# Projects.net
KiCad netlist of a schematic drawn in EAGLE
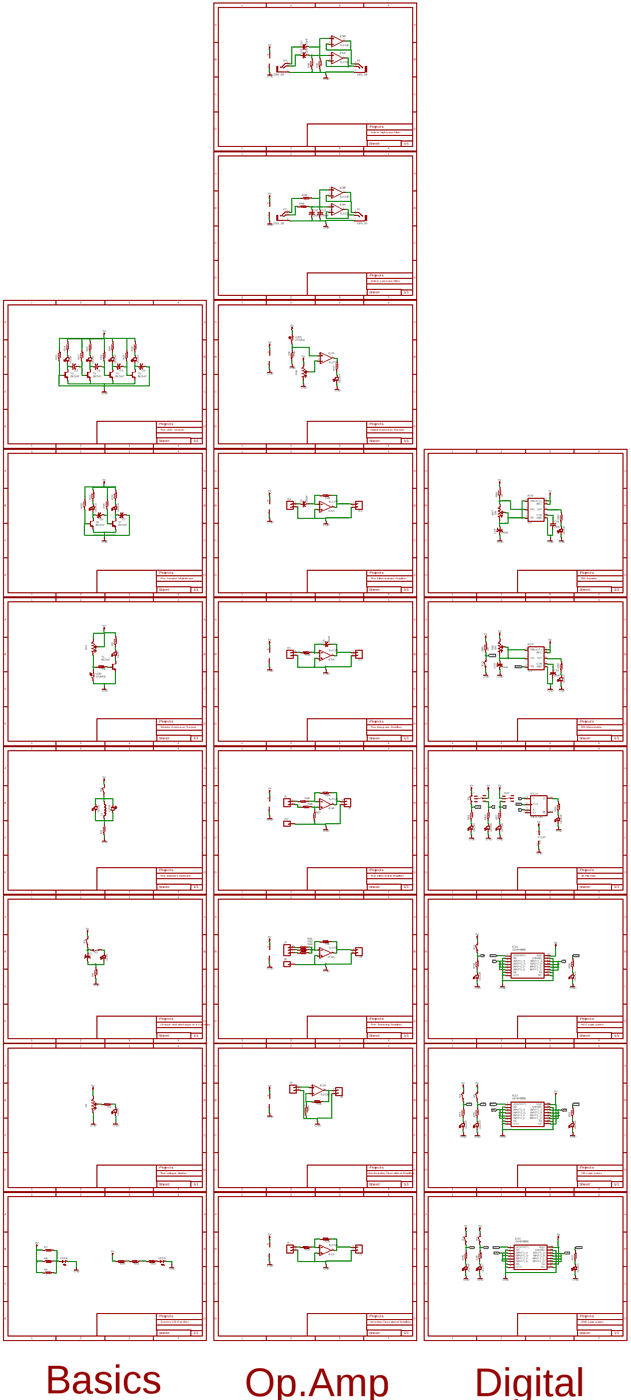
[diagram p0: schematic, sheet 1, overview]
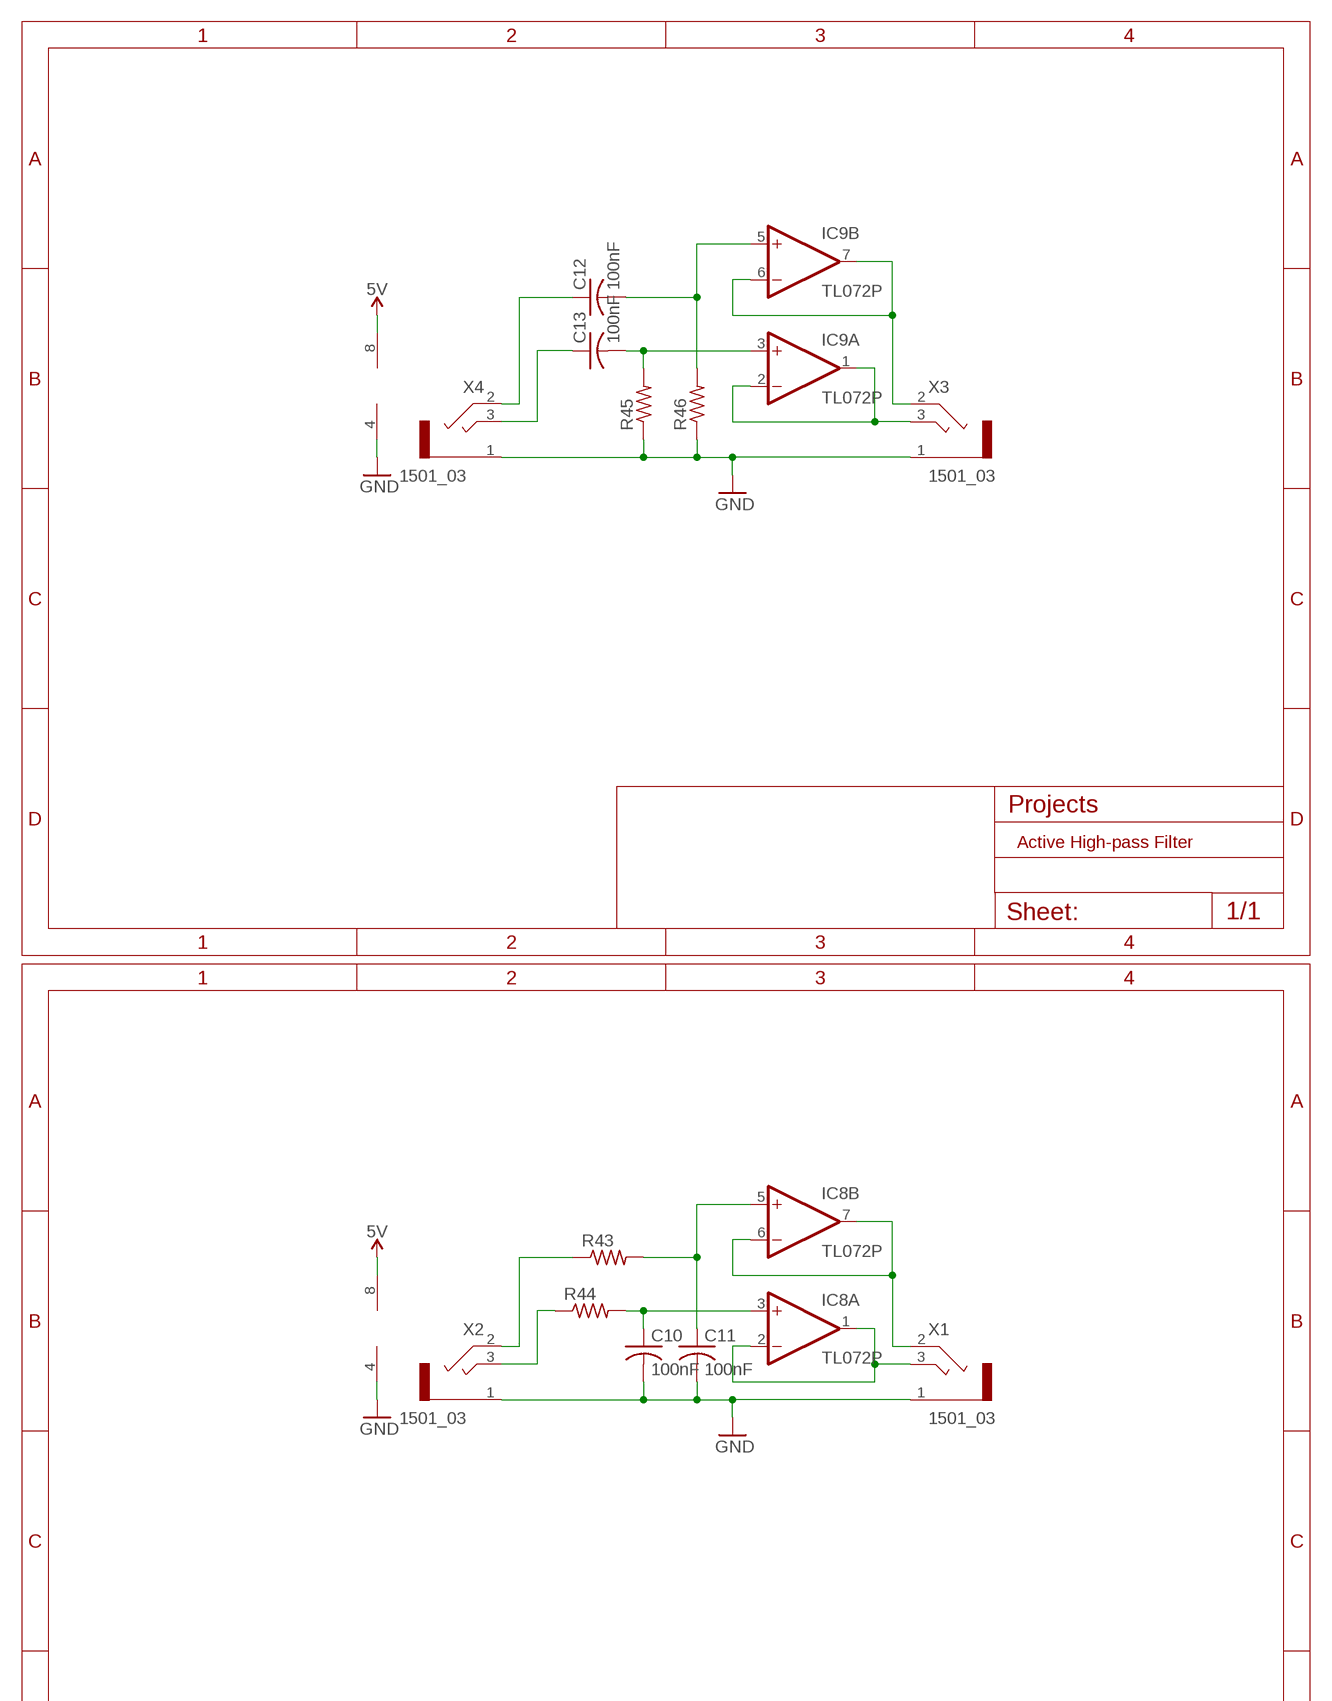
[diagram p1: schematic, sheet 1, part 1 of 7]
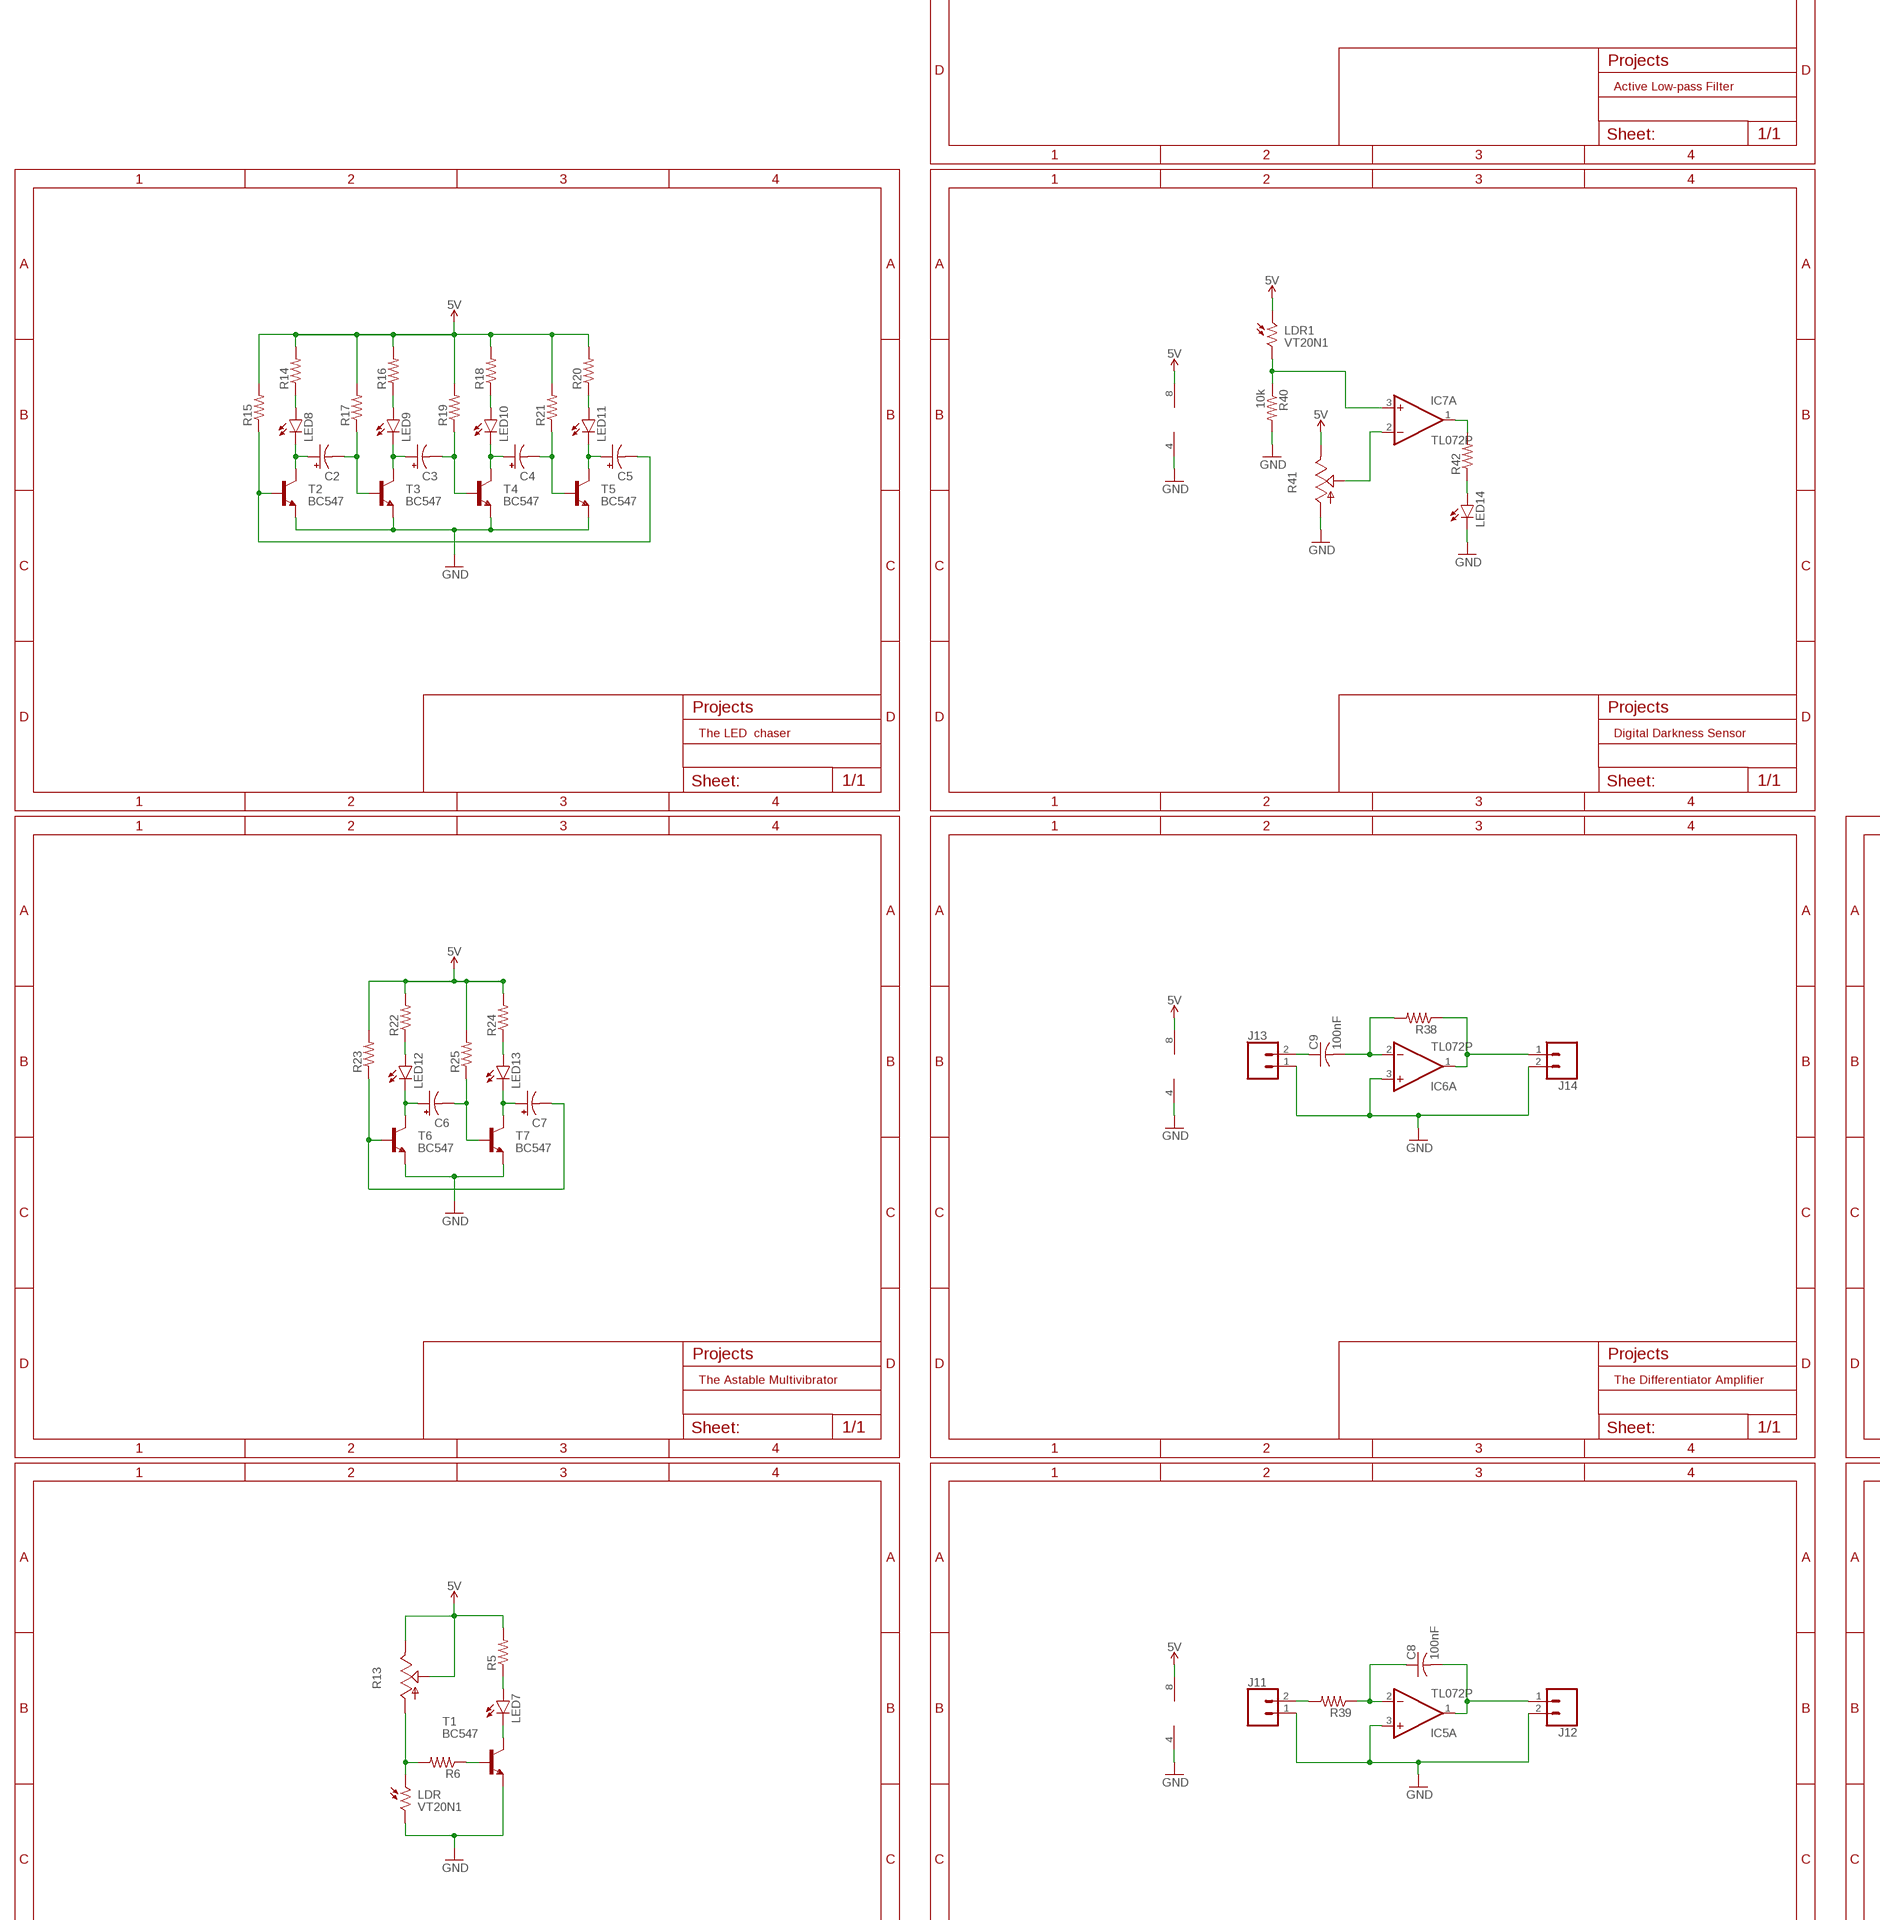
[diagram p2: schematic, sheet 1, part 2 of 7]
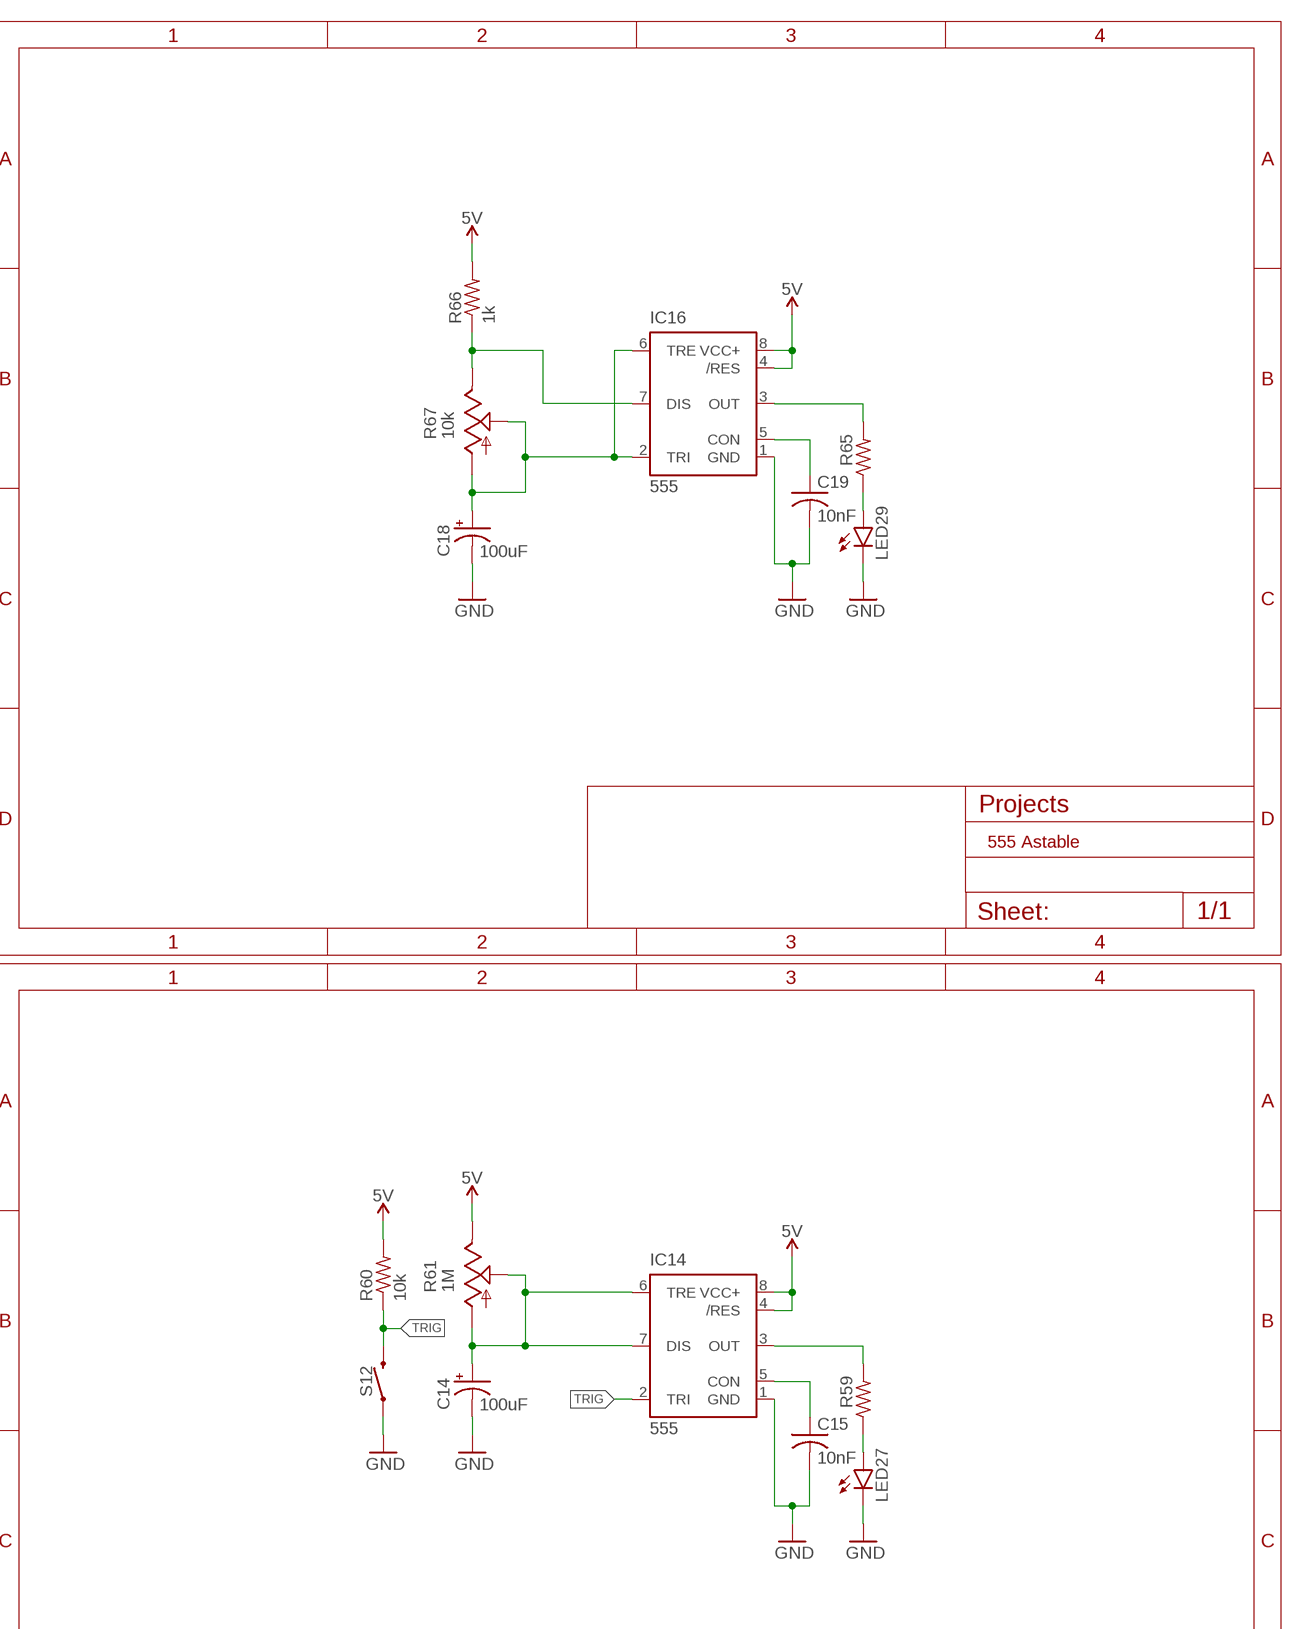
[diagram p3: schematic, sheet 1, part 3 of 7]
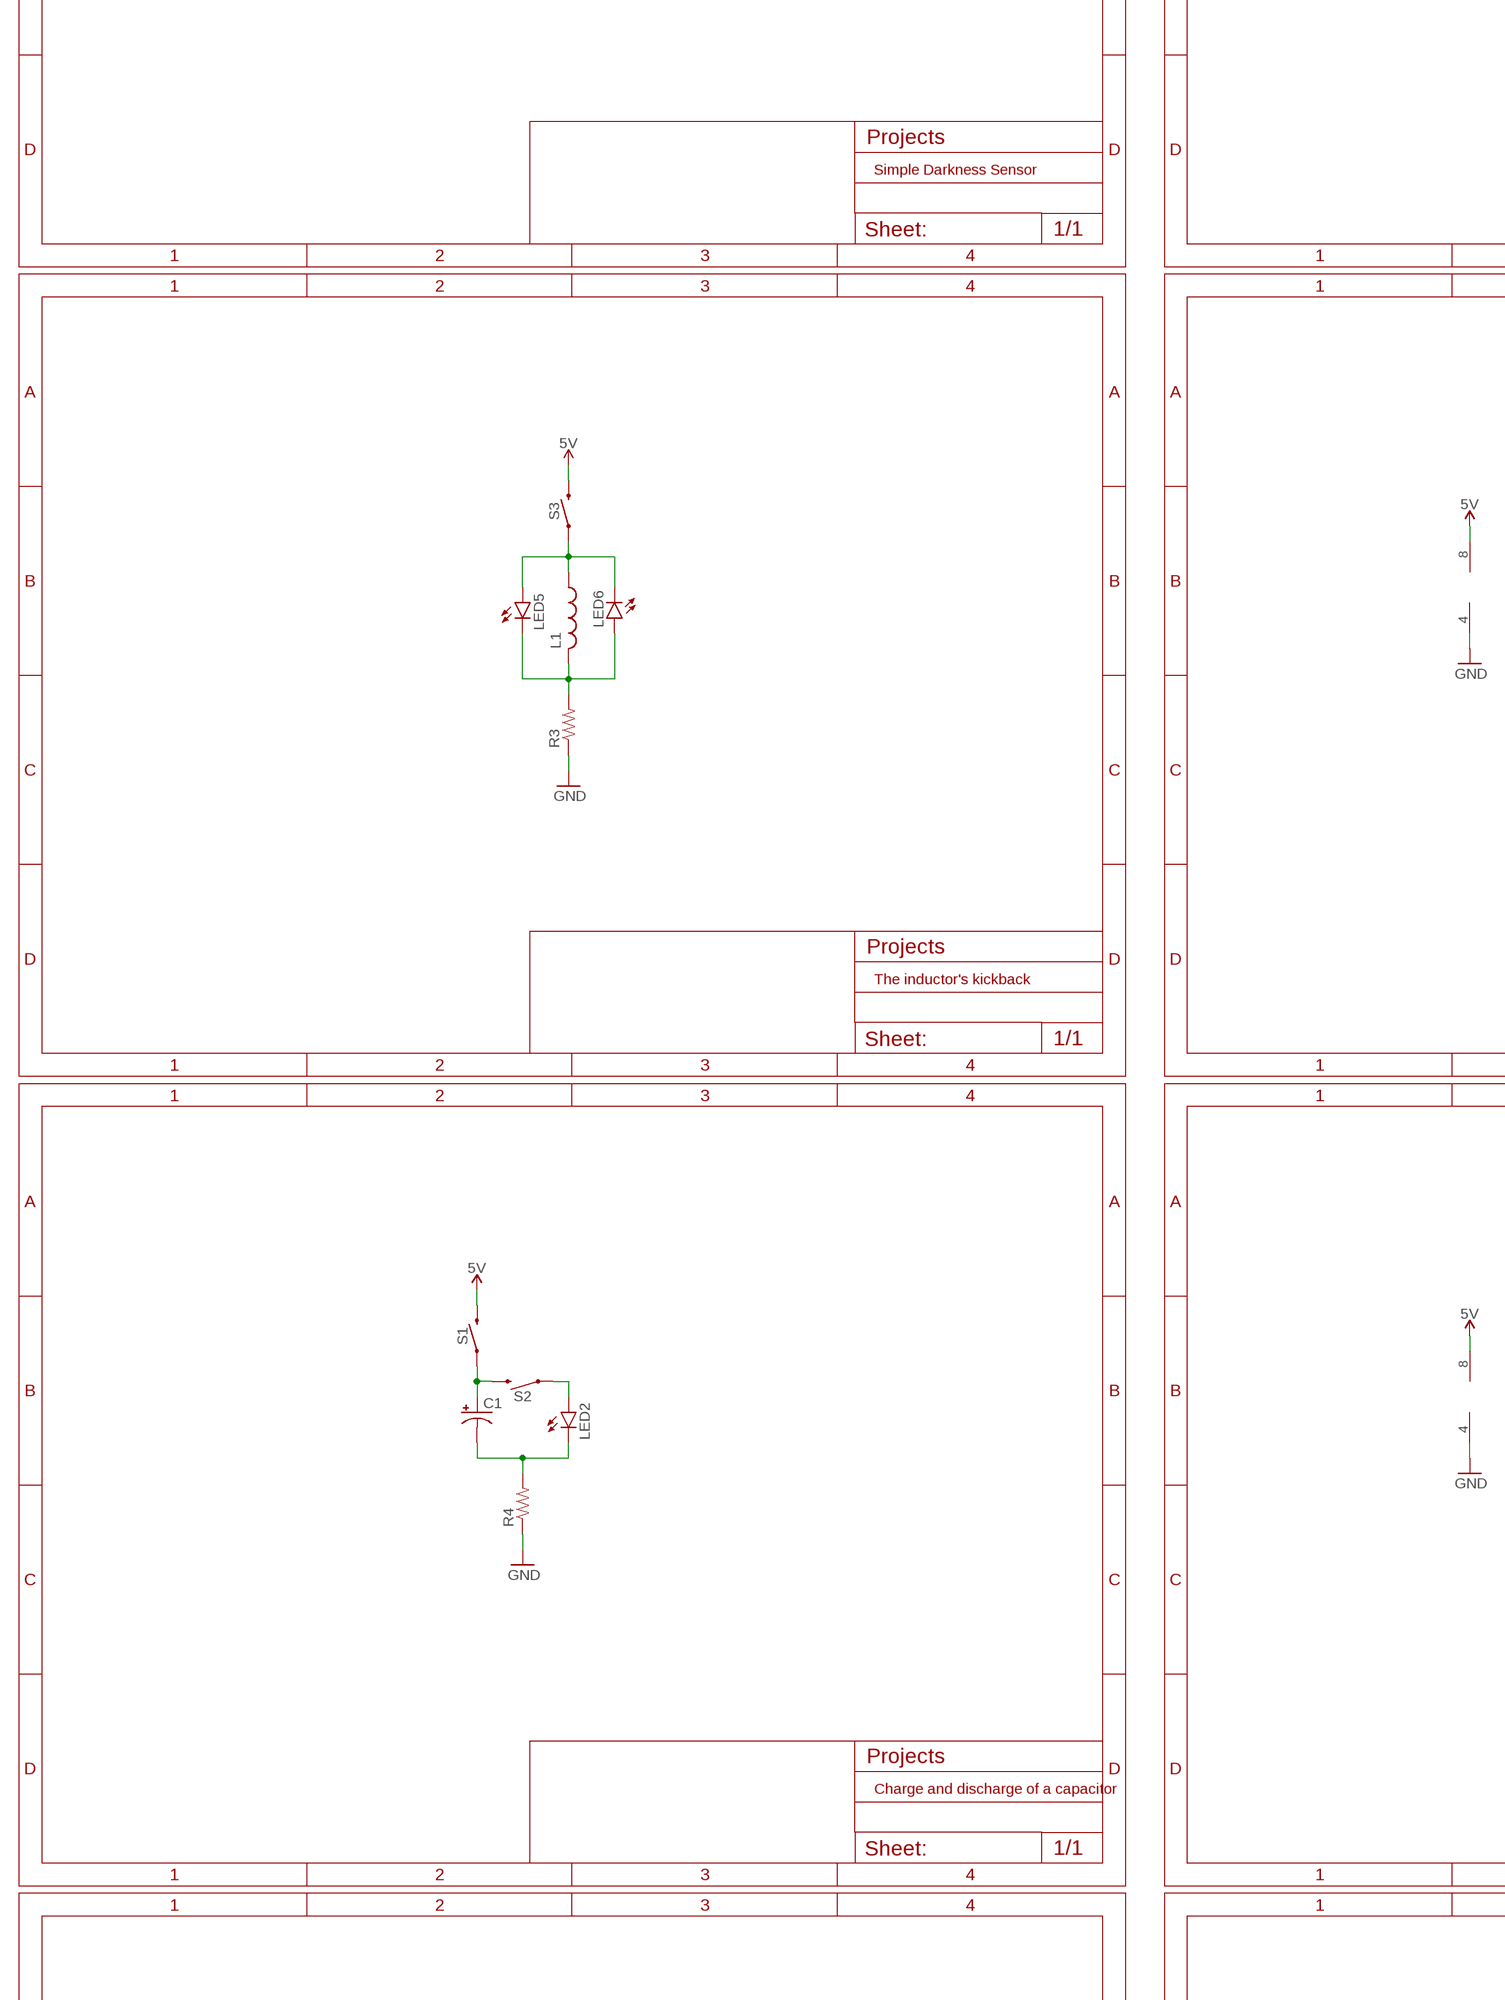
[diagram p4: schematic, sheet 1, part 4 of 7]
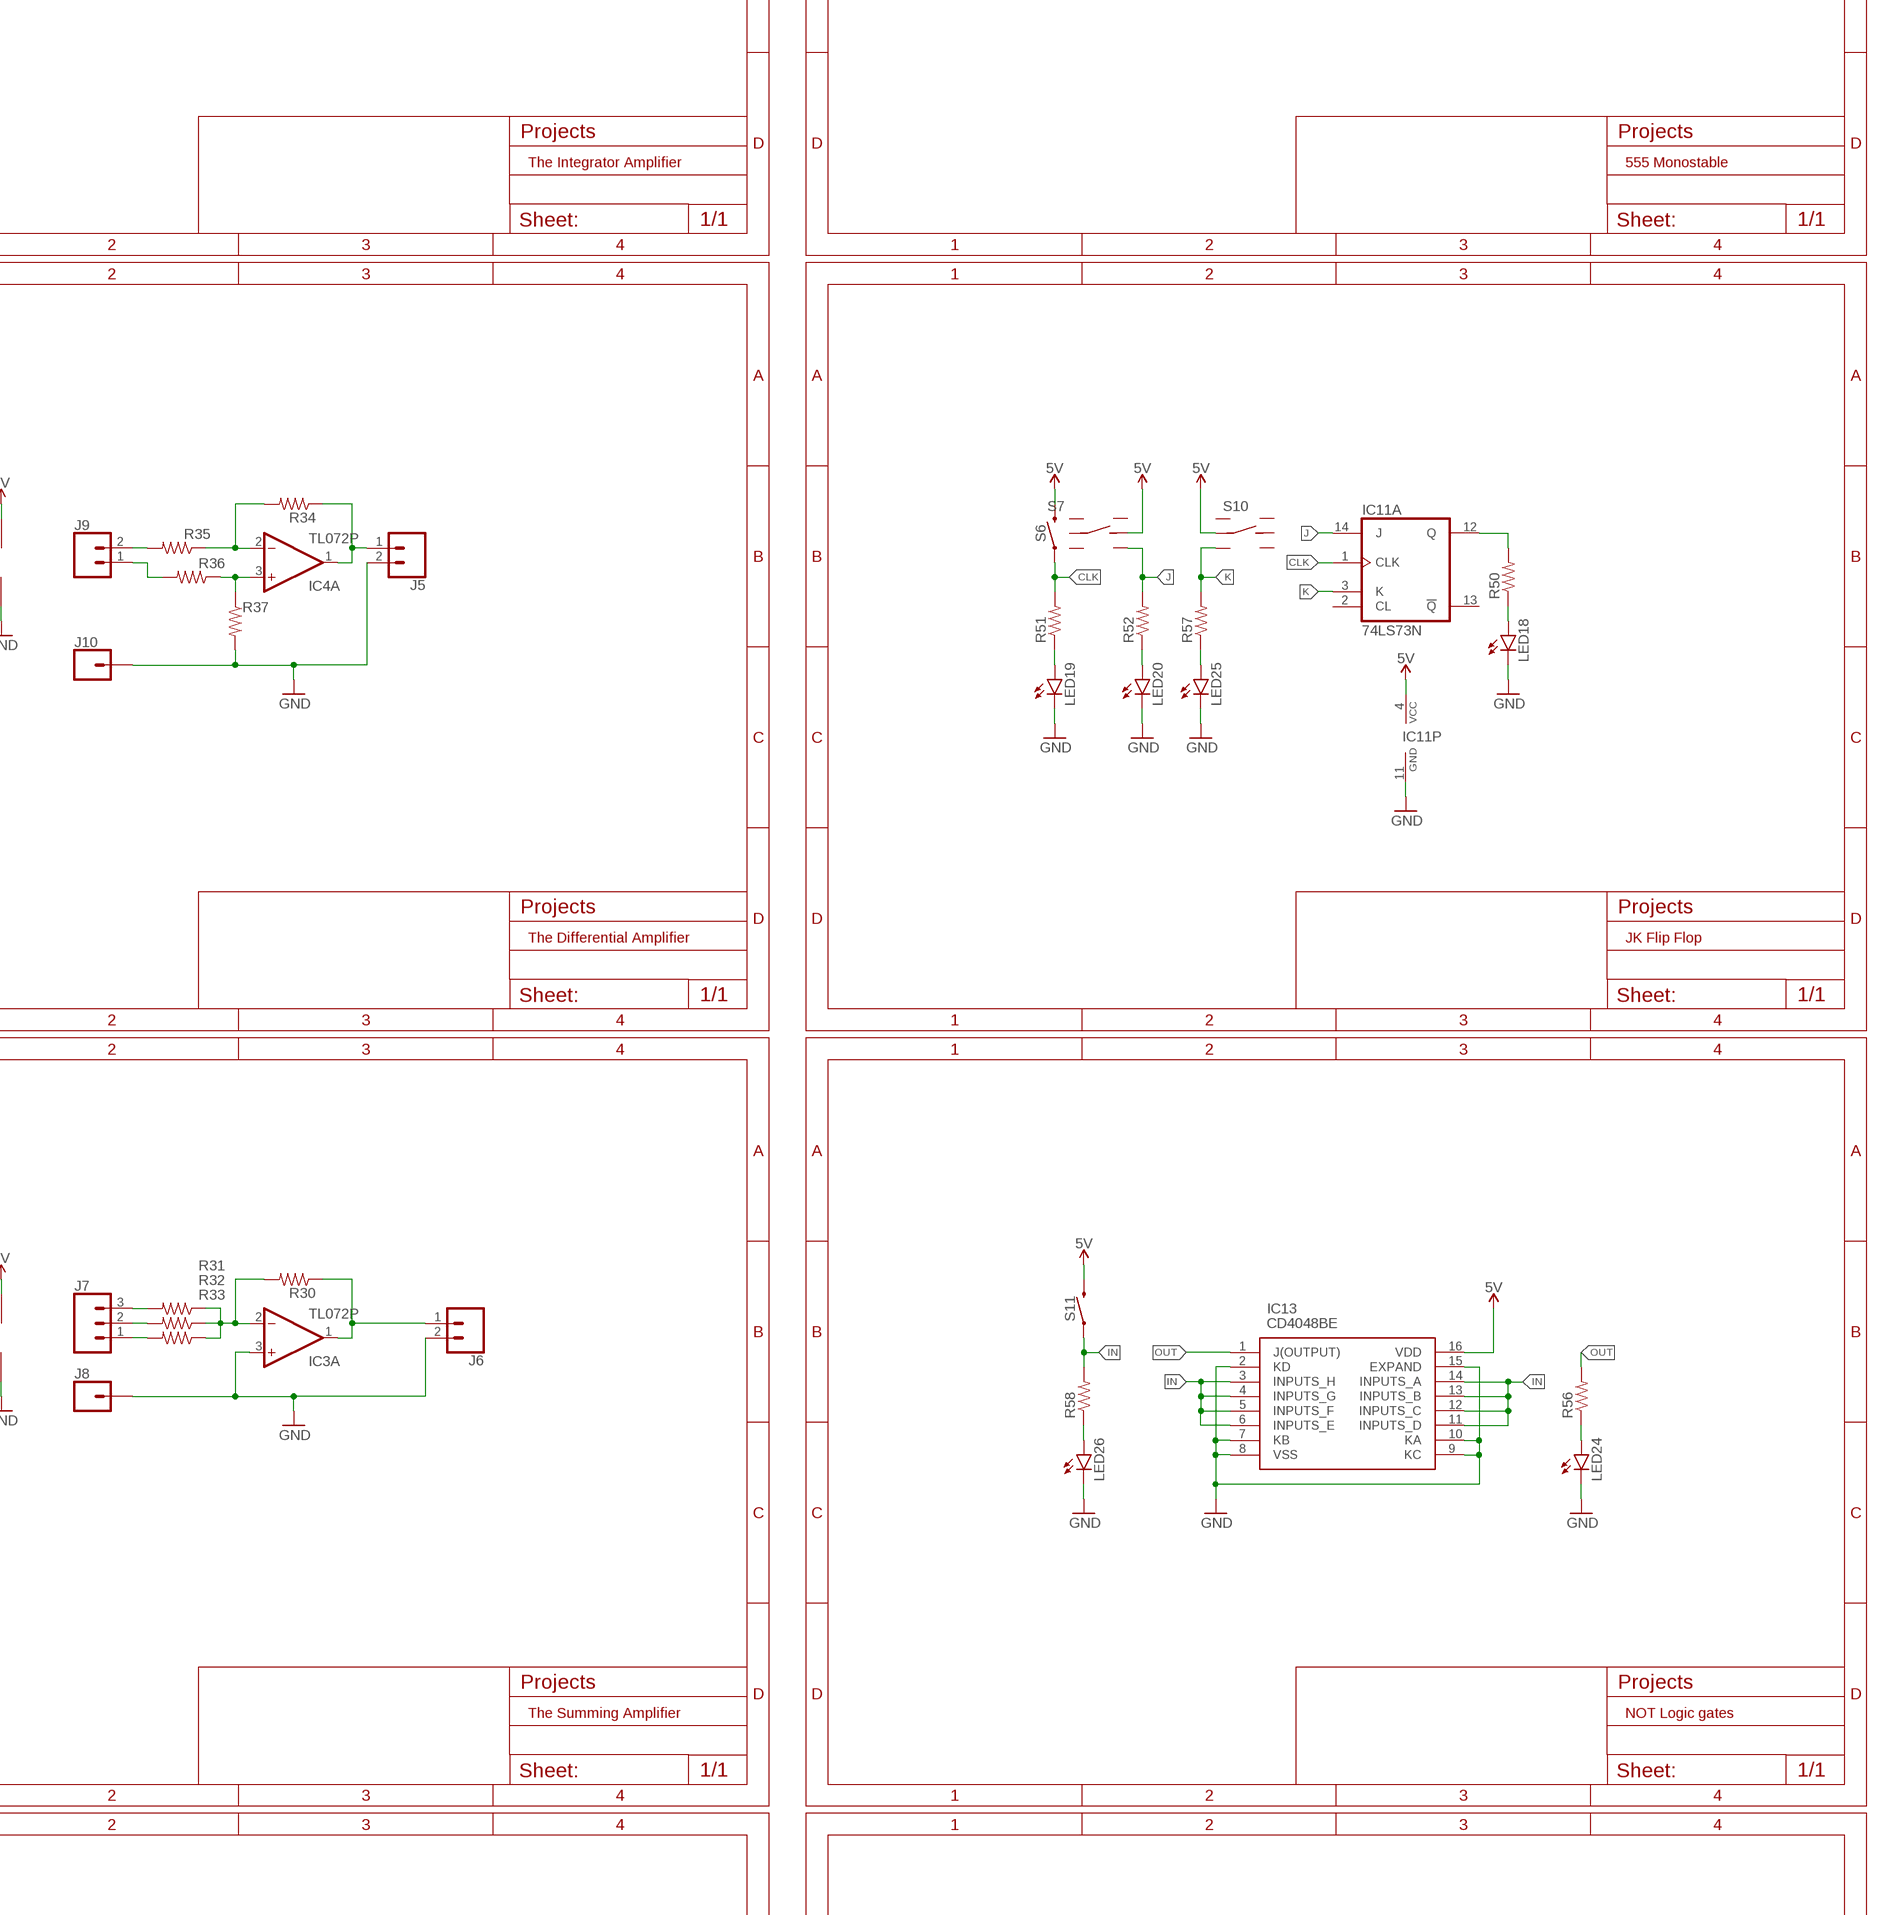
[diagram p5: schematic, sheet 1, part 5 of 7]
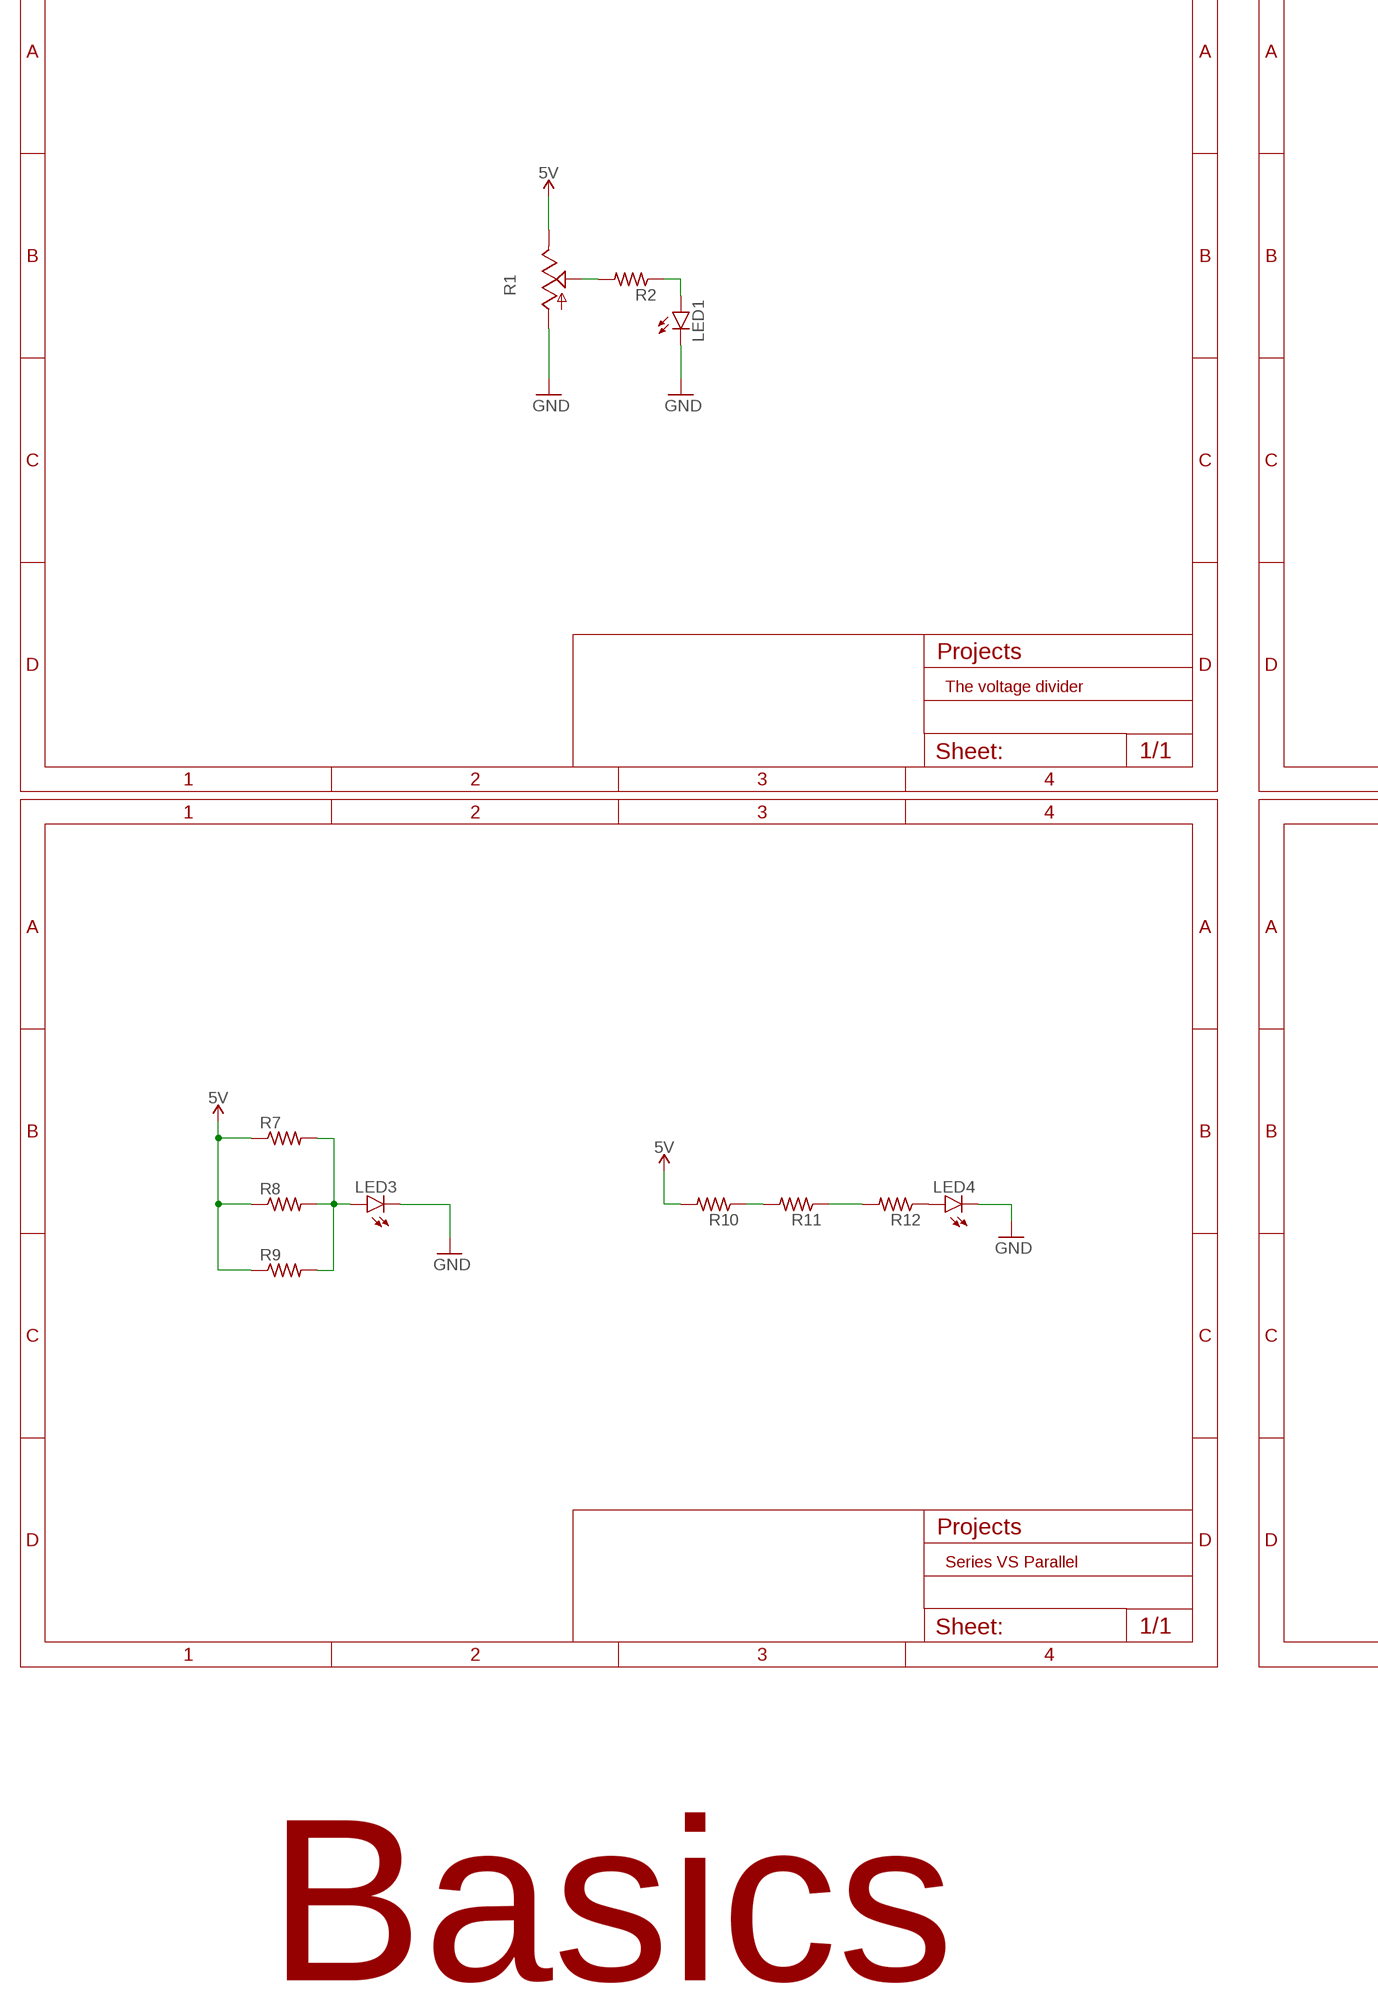
[diagram p6: schematic, sheet 1, part 6 of 7]
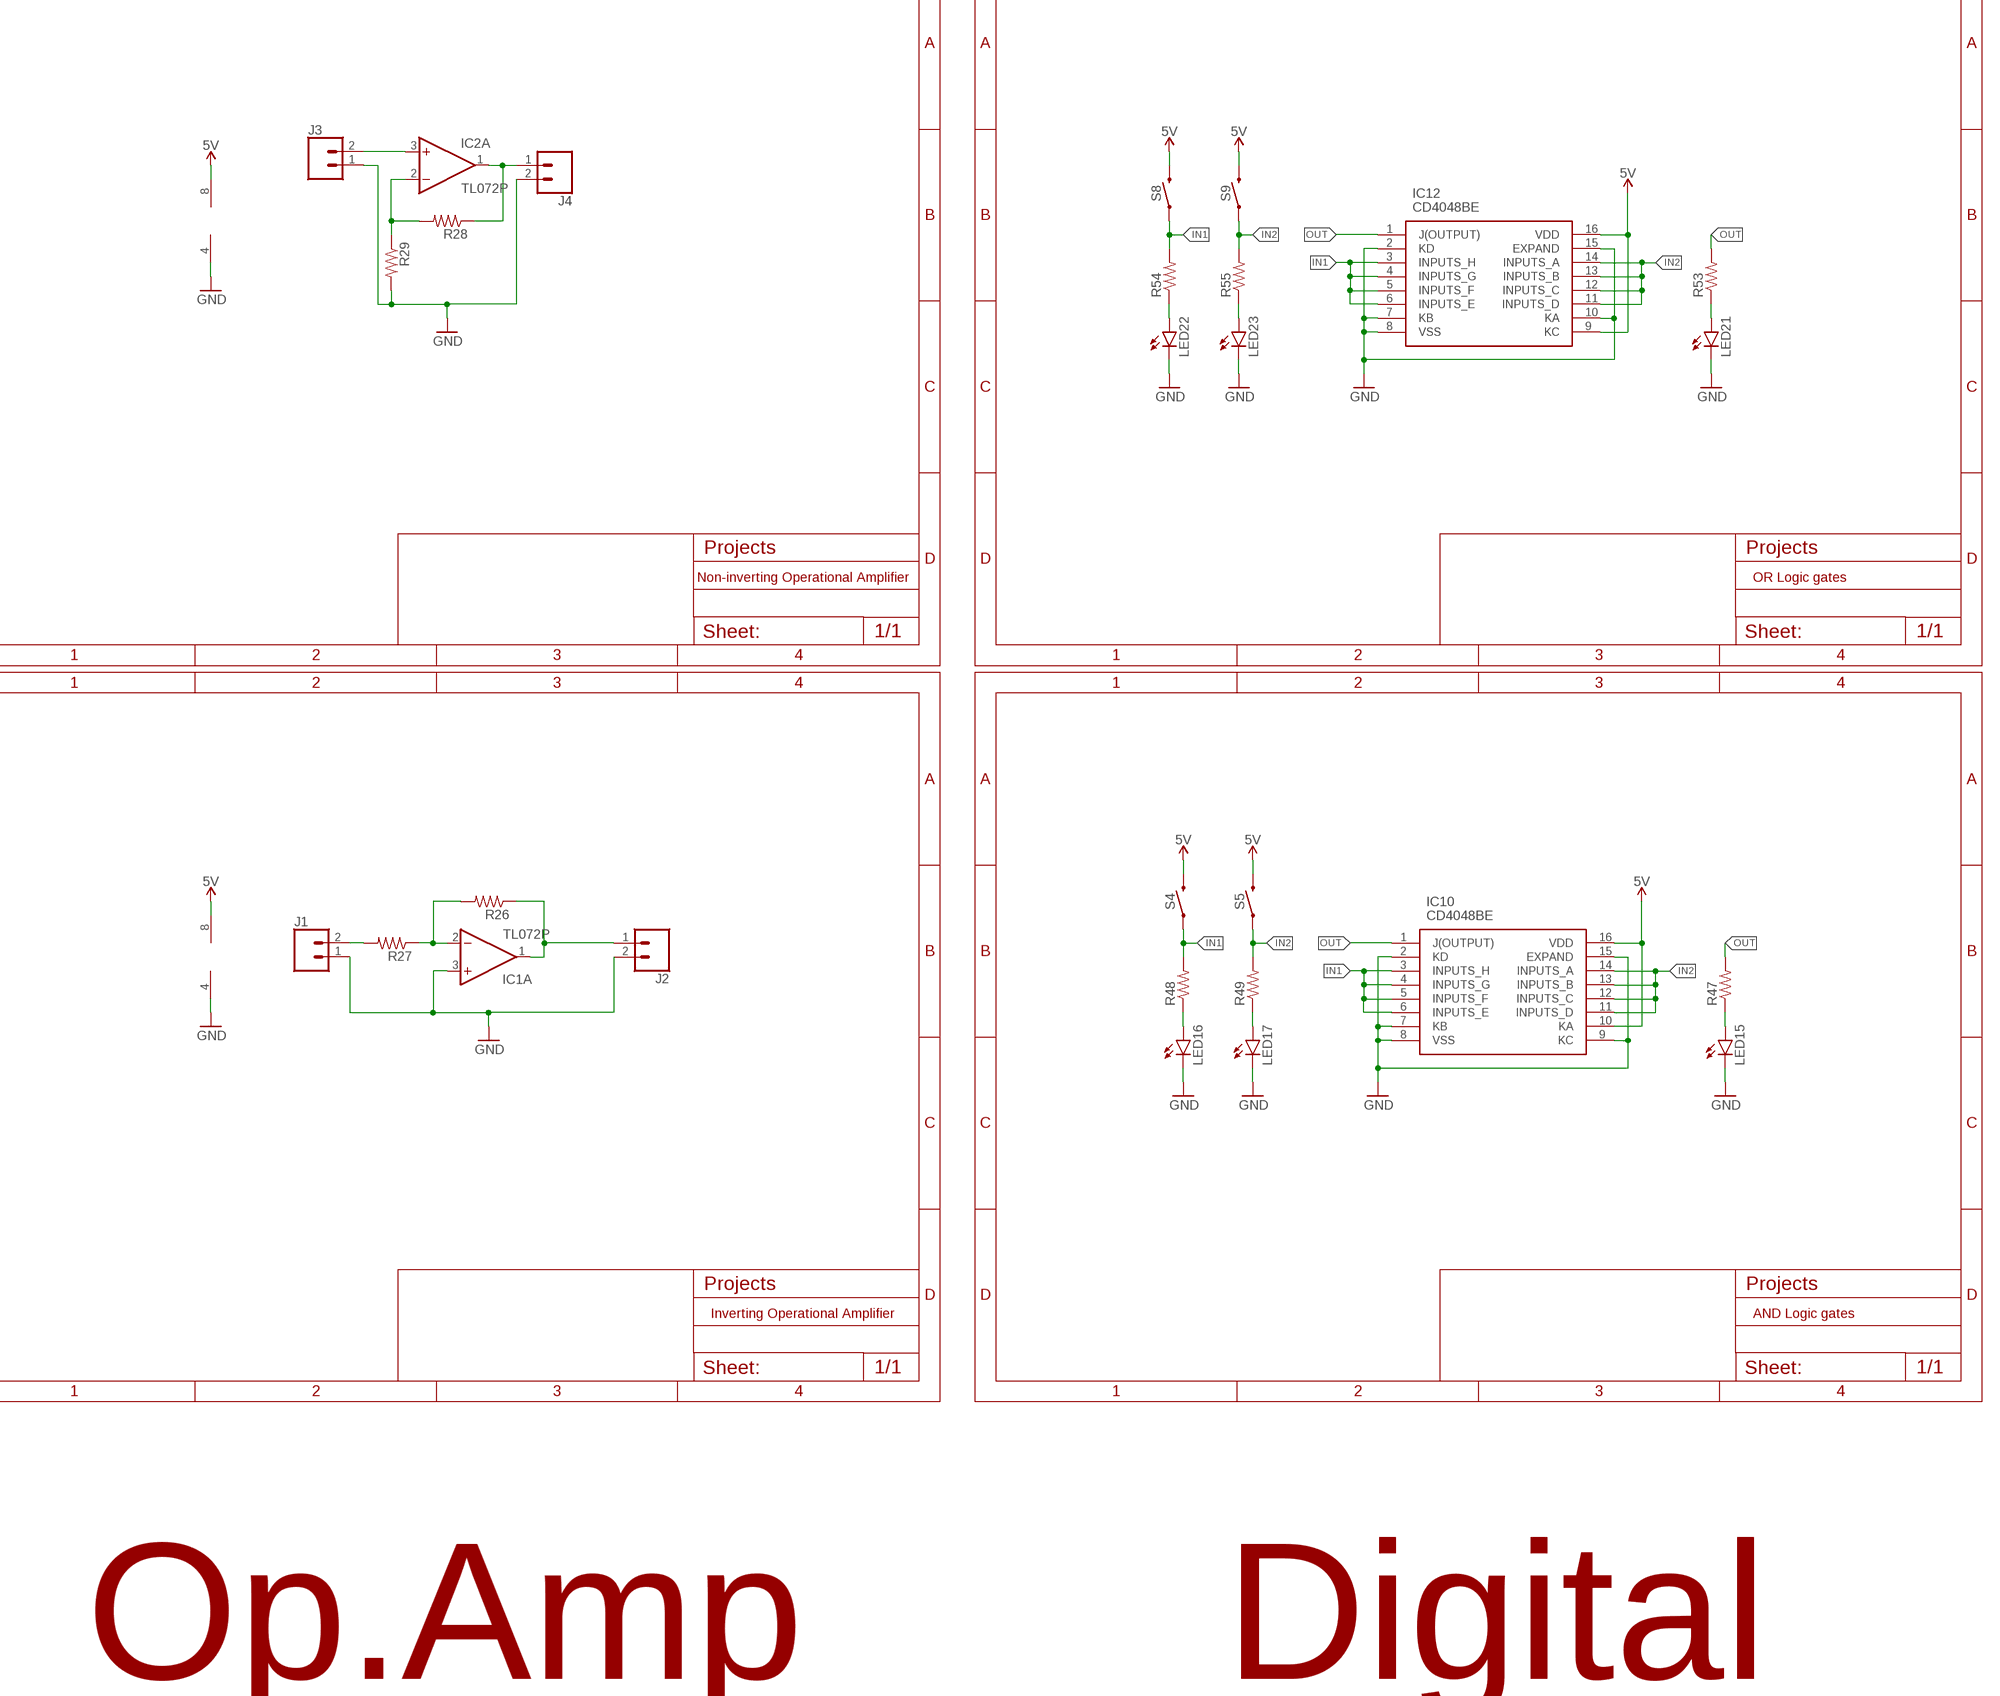
[diagram p7: schematic, sheet 1, part 7 of 7]

(export (version "E")
  (design (tool "Eeschema 10.0.6"))
  (components
    (comp (ref "C1")
      (value "CPOL-USE5-10.5")
      (footprint "eagle-import:E5-10,5")
      (libsource (lib "eagle-import") (part "CPOL-USE5-10.5"))
    )
    (comp (ref "C2")
      (value "CPOL-USE2.5-7")
      (footprint "eagle-import:E2,5-7")
      (libsource (lib "eagle-import") (part "rcl_334_CPOL-USE2.5-7"))
    )
    (comp (ref "C3")
      (value "CPOL-USE2.5-7")
      (footprint "eagle-import:E2,5-7")
      (libsource (lib "eagle-import") (part "rcl_334_CPOL-USE2.5-7"))
    )
    (comp (ref "C4")
      (value "CPOL-USE2.5-7")
      (footprint "eagle-import:E2,5-7")
      (libsource (lib "eagle-import") (part "rcl_334_CPOL-USE2.5-7"))
    )
    (comp (ref "C5")
      (value "CPOL-USE2.5-7")
      (footprint "eagle-import:E2,5-7")
      (libsource (lib "eagle-import") (part "rcl_334_CPOL-USE2.5-7"))
    )
    (comp (ref "C6")
      (value "CPOL-USE2.5-7")
      (footprint "eagle-import:E2,5-7")
      (libsource (lib "eagle-import") (part "rcl_334_CPOL-USE2.5-7"))
    )
    (comp (ref "C7")
      (value "CPOL-USE2.5-7")
      (footprint "eagle-import:E2,5-7")
      (libsource (lib "eagle-import") (part "rcl_334_CPOL-USE2.5-7"))
    )
    (comp (ref "C8")
      (value "100nF")
      (footprint "eagle-import:C050-025X075")
      (libsource (lib "eagle-import") (part "C-US050-025X075"))
    )
    (comp (ref "C9")
      (value "100nF")
      (footprint "eagle-import:C050-025X075")
      (libsource (lib "eagle-import") (part "C-US050-025X075"))
    )
    (comp (ref "C10")
      (value "100nF")
      (footprint "eagle-import:C050-025X075")
      (libsource (lib "eagle-import") (part "C-US050-025X075"))
    )
    (comp (ref "C11")
      (value "100nF")
      (footprint "eagle-import:C050-025X075")
      (libsource (lib "eagle-import") (part "C-US050-025X075"))
    )
    (comp (ref "C12")
      (value "100nF")
      (footprint "eagle-import:C050-025X075")
      (libsource (lib "eagle-import") (part "C-US050-025X075"))
    )
    (comp (ref "C13")
      (value "100nF")
      (footprint "eagle-import:C050-025X075")
      (libsource (lib "eagle-import") (part "C-US050-025X075"))
    )
    (comp (ref "C14")
      (value "100uF")
      (footprint "eagle-import:E2,5-7")
      (libsource (lib "eagle-import") (part "rcl_334_CPOL-USE2.5-7"))
    )
    (comp (ref "C15")
      (value "10nF")
      (footprint "eagle-import:C050-025X075")
      (libsource (lib "eagle-import") (part "C-US050-025X075"))
    )
    (comp (ref "C18")
      (value "100uF")
      (footprint "eagle-import:E2,5-7")
      (libsource (lib "eagle-import") (part "rcl_334_CPOL-USE2.5-7"))
    )
    (comp (ref "C19")
      (value "10nF")
      (footprint "eagle-import:C050-025X075")
      (libsource (lib "eagle-import") (part "C-US050-025X075"))
    )
    (comp (ref "IC1")
      (value "TL072P")
      (footprint "eagle-import:DIL08")
      (libsource (lib "eagle-import") (part "TL072P"))
    )
    (comp (ref "IC2")
      (value "TL072P")
      (footprint "eagle-import:DIL08")
      (libsource (lib "eagle-import") (part "TL072P"))
    )
    (comp (ref "IC3")
      (value "TL072P")
      (footprint "eagle-import:DIL08")
      (libsource (lib "eagle-import") (part "TL072P"))
    )
    (comp (ref "IC4")
      (value "TL072P")
      (footprint "eagle-import:DIL08")
      (libsource (lib "eagle-import") (part "TL072P"))
    )
    (comp (ref "IC5")
      (value "TL072P")
      (footprint "eagle-import:DIL08")
      (libsource (lib "eagle-import") (part "TL072P"))
    )
    (comp (ref "IC6")
      (value "TL072P")
      (footprint "eagle-import:DIL08")
      (libsource (lib "eagle-import") (part "TL072P"))
    )
    (comp (ref "IC7")
      (value "TL072P")
      (footprint "eagle-import:DIL08")
      (libsource (lib "eagle-import") (part "TL072P"))
    )
    (comp (ref "IC8")
      (value "TL072P")
      (footprint "eagle-import:DIL08")
      (libsource (lib "eagle-import") (part "TL072P"))
    )
    (comp (ref "IC9")
      (value "TL072P")
      (footprint "eagle-import:DIL08")
      (libsource (lib "eagle-import") (part "TL072P"))
    )
    (comp (ref "IC10")
      (value "CD4048BE")
      (footprint "eagle-import:DIP794W53P254L1930H508Q16N")
      (fields (field (name "MOUSER_PART_NUMBER") "595-CD4048BE"))
      (libsource (lib "eagle-import") (part "CD4048BE"))
    )
    (comp (ref "IC11")
      (value "74LS73N")
      (footprint "eagle-import:DIL14")
      (libsource (lib "eagle-import") (part "7473NLS"))
    )
    (comp (ref "IC12")
      (value "CD4048BE")
      (footprint "eagle-import:DIP794W53P254L1930H508Q16N")
      (fields (field (name "MOUSER_PART_NUMBER") "595-CD4048BE"))
      (libsource (lib "eagle-import") (part "CD4048BE"))
    )
    (comp (ref "IC13")
      (value "CD4048BE")
      (footprint "eagle-import:DIP794W53P254L1930H508Q16N")
      (fields (field (name "MOUSER_PART_NUMBER") "595-CD4048BE"))
      (libsource (lib "eagle-import") (part "CD4048BE"))
    )
    (comp (ref "IC14")
      (value "555")
      (footprint "eagle-import:DIP08-KIT")
      (libsource (lib "eagle-import") (part "555KIT"))
    )
    (comp (ref "IC16")
      (value "555")
      (footprint "eagle-import:DIP08-KIT")
      (libsource (lib "eagle-import") (part "555KIT"))
    )
    (comp (ref "J1")
      (value "CONN_02")
      (footprint "eagle-import:1X02")
      (libsource (lib "eagle-import") (part "CONN_02"))
    )
    (comp (ref "J2")
      (value "CONN_02")
      (footprint "eagle-import:1X02")
      (libsource (lib "eagle-import") (part "CONN_02"))
    )
    (comp (ref "J3")
      (value "CONN_02")
      (footprint "eagle-import:1X02")
      (libsource (lib "eagle-import") (part "CONN_02"))
    )
    (comp (ref "J4")
      (value "CONN_02")
      (footprint "eagle-import:1X02")
      (libsource (lib "eagle-import") (part "CONN_02"))
    )
    (comp (ref "J5")
      (value "CONN_02")
      (footprint "eagle-import:1X02")
      (libsource (lib "eagle-import") (part "CONN_02"))
    )
    (comp (ref "J6")
      (value "CONN_02")
      (footprint "eagle-import:1X02")
      (libsource (lib "eagle-import") (part "CONN_02"))
    )
    (comp (ref "J7")
      (value "455-1750-1-ND")
      (footprint "eagle-import:1X03")
      (libsource (lib "eagle-import") (part "CONN_03"))
    )
    (comp (ref "J8")
      (value "CONN_01")
      (footprint "eagle-import:1X01")
      (libsource (lib "eagle-import") (part "CONN_01"))
    )
    (comp (ref "J9")
      (value "CONN_02")
      (footprint "eagle-import:1X02")
      (libsource (lib "eagle-import") (part "CONN_02"))
    )
    (comp (ref "J10")
      (value "CONN_01")
      (footprint "eagle-import:1X01")
      (libsource (lib "eagle-import") (part "CONN_01"))
    )
    (comp (ref "J11")
      (value "CONN_02")
      (footprint "eagle-import:1X02")
      (libsource (lib "eagle-import") (part "CONN_02"))
    )
    (comp (ref "J12")
      (value "CONN_02")
      (footprint "eagle-import:1X02")
      (libsource (lib "eagle-import") (part "CONN_02"))
    )
    (comp (ref "J13")
      (value "CONN_02")
      (footprint "eagle-import:1X02")
      (libsource (lib "eagle-import") (part "CONN_02"))
    )
    (comp (ref "J14")
      (value "CONN_02")
      (footprint "eagle-import:1X02")
      (libsource (lib "eagle-import") (part "CONN_02"))
    )
    (comp (ref "L1")
      (value "L-US6000-XXX-RC")
      (footprint "eagle-import:6000-XXXX-RC")
      (libsource (lib "eagle-import") (part "L-US6000-XXX-RC"))
    )
    (comp (ref "LDR")
      (value "VT20N1")
      (footprint "eagle-import:TO46-VT200")
      (libsource (lib "eagle-import") (part "VT20N1"))
    )
    (comp (ref "LDR1")
      (value "VT20N1")
      (footprint "eagle-import:TO46-VT200")
      (libsource (lib "eagle-import") (part "VT20N1"))
    )
    (comp (ref "LED1")
      (value "LED5MM")
      (footprint "eagle-import:LED5MM")
      (libsource (lib "eagle-import") (part "LED5MM"))
    )
    (comp (ref "LED2")
      (value "LED5MM")
      (footprint "eagle-import:LED5MM")
      (libsource (lib "eagle-import") (part "LED5MM"))
    )
    (comp (ref "LED3")
      (value "LED5MM")
      (footprint "eagle-import:LED5MM")
      (libsource (lib "eagle-import") (part "LED5MM"))
    )
    (comp (ref "LED4")
      (value "LED5MM")
      (footprint "eagle-import:LED5MM")
      (libsource (lib "eagle-import") (part "LED5MM"))
    )
    (comp (ref "LED5")
      (value "LED5MM")
      (footprint "eagle-import:LED5MM")
      (libsource (lib "eagle-import") (part "LED5MM"))
    )
    (comp (ref "LED6")
      (value "LED5MM")
      (footprint "eagle-import:LED5MM")
      (libsource (lib "eagle-import") (part "LED5MM"))
    )
    (comp (ref "LED7")
      (value "LED5MM")
      (footprint "eagle-import:LED5MM")
      (libsource (lib "eagle-import") (part "LED5MM"))
    )
    (comp (ref "LED8")
      (value "LED5MM")
      (footprint "eagle-import:LED5MM")
      (libsource (lib "eagle-import") (part "LED5MM"))
    )
    (comp (ref "LED9")
      (value "LED5MM")
      (footprint "eagle-import:LED5MM")
      (libsource (lib "eagle-import") (part "LED5MM"))
    )
    (comp (ref "LED10")
      (value "LED5MM")
      (footprint "eagle-import:LED5MM")
      (libsource (lib "eagle-import") (part "LED5MM"))
    )
    (comp (ref "LED11")
      (value "LED5MM")
      (footprint "eagle-import:LED5MM")
      (libsource (lib "eagle-import") (part "LED5MM"))
    )
    (comp (ref "LED12")
      (value "LED5MM")
      (footprint "eagle-import:LED5MM")
      (libsource (lib "eagle-import") (part "LED5MM"))
    )
    (comp (ref "LED13")
      (value "LED5MM")
      (footprint "eagle-import:LED5MM")
      (libsource (lib "eagle-import") (part "LED5MM"))
    )
    (comp (ref "LED14")
      (value "LED5MM")
      (footprint "eagle-import:LED5MM")
      (libsource (lib "eagle-import") (part "LED5MM"))
    )
    (comp (ref "LED15")
      (value "LED5MM")
      (footprint "eagle-import:LED5MM")
      (libsource (lib "eagle-import") (part "LED5MM"))
    )
    (comp (ref "LED16")
      (value "LED5MM")
      (footprint "eagle-import:LED5MM")
      (libsource (lib "eagle-import") (part "LED5MM"))
    )
    (comp (ref "LED17")
      (value "LED5MM")
      (footprint "eagle-import:LED5MM")
      (libsource (lib "eagle-import") (part "LED5MM"))
    )
    (comp (ref "LED18")
      (value "LED5MM")
      (footprint "eagle-import:LED5MM")
      (libsource (lib "eagle-import") (part "LED5MM"))
    )
    (comp (ref "LED19")
      (value "LED5MM")
      (footprint "eagle-import:LED5MM")
      (libsource (lib "eagle-import") (part "LED5MM"))
    )
    (comp (ref "LED20")
      (value "LED5MM")
      (footprint "eagle-import:LED5MM")
      (libsource (lib "eagle-import") (part "LED5MM"))
    )
    (comp (ref "LED21")
      (value "LED5MM")
      (footprint "eagle-import:LED5MM")
      (libsource (lib "eagle-import") (part "LED5MM"))
    )
    (comp (ref "LED22")
      (value "LED5MM")
      (footprint "eagle-import:LED5MM")
      (libsource (lib "eagle-import") (part "LED5MM"))
    )
    (comp (ref "LED23")
      (value "LED5MM")
      (footprint "eagle-import:LED5MM")
      (libsource (lib "eagle-import") (part "LED5MM"))
    )
    (comp (ref "LED24")
      (value "LED5MM")
      (footprint "eagle-import:LED5MM")
      (libsource (lib "eagle-import") (part "LED5MM"))
    )
    (comp (ref "LED25")
      (value "LED5MM")
      (footprint "eagle-import:LED5MM")
      (libsource (lib "eagle-import") (part "LED5MM"))
    )
    (comp (ref "LED26")
      (value "LED5MM")
      (footprint "eagle-import:LED5MM")
      (libsource (lib "eagle-import") (part "LED5MM"))
    )
    (comp (ref "LED27")
      (value "LED5MM")
      (footprint "eagle-import:LED5MM")
      (libsource (lib "eagle-import") (part "LED5MM"))
    )
    (comp (ref "LED29")
      (value "LED5MM")
      (footprint "eagle-import:LED5MM")
      (libsource (lib "eagle-import") (part "LED5MM"))
    )
    (comp (ref "R1")
      (value "TRIM_US-S63P")
      (footprint "eagle-import:S63P")
      (libsource (lib "eagle-import") (part "TRIM_US-S63P"))
    )
    (comp (ref "R2")
      (value "R-US_0204/7")
      (footprint "eagle-import:0204_7")
      (libsource (lib "eagle-import") (part "R-US_0204/7"))
    )
    (comp (ref "R3")
      (value "R-US_0204/7")
      (footprint "eagle-import:0204_7")
      (libsource (lib "eagle-import") (part "R-US_0204/7"))
    )
    (comp (ref "R4")
      (value "R-US_0204/7")
      (footprint "eagle-import:0204_7")
      (libsource (lib "eagle-import") (part "R-US_0204/7"))
    )
    (comp (ref "R5")
      (value "R-US_0204/7")
      (footprint "eagle-import:0204_7")
      (libsource (lib "eagle-import") (part "R-US_0204/7"))
    )
    (comp (ref "R6")
      (value "R-US_0204/7")
      (footprint "eagle-import:0204_7")
      (libsource (lib "eagle-import") (part "R-US_0204/7"))
    )
    (comp (ref "R7")
      (value "R-US_0204/7")
      (footprint "eagle-import:0204_7")
      (libsource (lib "eagle-import") (part "R-US_0204/7"))
    )
    (comp (ref "R8")
      (value "R-US_0204/7")
      (footprint "eagle-import:0204_7")
      (libsource (lib "eagle-import") (part "R-US_0204/7"))
    )
    (comp (ref "R9")
      (value "R-US_0204/7")
      (footprint "eagle-import:0204_7")
      (libsource (lib "eagle-import") (part "R-US_0204/7"))
    )
    (comp (ref "R10")
      (value "R-US_0204/7")
      (footprint "eagle-import:0204_7")
      (libsource (lib "eagle-import") (part "R-US_0204/7"))
    )
    (comp (ref "R11")
      (value "R-US_0204/7")
      (footprint "eagle-import:0204_7")
      (libsource (lib "eagle-import") (part "R-US_0204/7"))
    )
    (comp (ref "R12")
      (value "R-US_0204/7")
      (footprint "eagle-import:0204_7")
      (libsource (lib "eagle-import") (part "R-US_0204/7"))
    )
    (comp (ref "R13")
      (value "TRIM_US-S63P")
      (footprint "eagle-import:S63P")
      (libsource (lib "eagle-import") (part "TRIM_US-S63P"))
    )
    (comp (ref "R14")
      (value "R-US_0204/7")
      (footprint "eagle-import:0204_7")
      (libsource (lib "eagle-import") (part "R-US_0204/7"))
    )
    (comp (ref "R15")
      (value "R-US_0204/7")
      (footprint "eagle-import:0204_7")
      (libsource (lib "eagle-import") (part "R-US_0204/7"))
    )
    (comp (ref "R16")
      (value "R-US_0204/7")
      (footprint "eagle-import:0204_7")
      (libsource (lib "eagle-import") (part "R-US_0204/7"))
    )
    (comp (ref "R17")
      (value "R-US_0204/7")
      (footprint "eagle-import:0204_7")
      (libsource (lib "eagle-import") (part "R-US_0204/7"))
    )
    (comp (ref "R18")
      (value "R-US_0204/7")
      (footprint "eagle-import:0204_7")
      (libsource (lib "eagle-import") (part "R-US_0204/7"))
    )
    (comp (ref "R19")
      (value "R-US_0204/7")
      (footprint "eagle-import:0204_7")
      (libsource (lib "eagle-import") (part "R-US_0204/7"))
    )
    (comp (ref "R20")
      (value "R-US_0204/7")
      (footprint "eagle-import:0204_7")
      (libsource (lib "eagle-import") (part "R-US_0204/7"))
    )
    (comp (ref "R21")
      (value "R-US_0204/7")
      (footprint "eagle-import:0204_7")
      (libsource (lib "eagle-import") (part "R-US_0204/7"))
    )
    (comp (ref "R22")
      (value "R-US_0204/7")
      (footprint "eagle-import:0204_7")
      (libsource (lib "eagle-import") (part "R-US_0204/7"))
    )
    (comp (ref "R23")
      (value "R-US_0204/7")
      (footprint "eagle-import:0204_7")
      (libsource (lib "eagle-import") (part "R-US_0204/7"))
    )
    (comp (ref "R24")
      (value "R-US_0204/7")
      (footprint "eagle-import:0204_7")
      (libsource (lib "eagle-import") (part "R-US_0204/7"))
    )
    (comp (ref "R25")
      (value "R-US_0204/7")
      (footprint "eagle-import:0204_7")
      (libsource (lib "eagle-import") (part "R-US_0204/7"))
    )
    (comp (ref "R26")
      (value "R-US_0204/7")
      (footprint "eagle-import:0204_7")
      (libsource (lib "eagle-import") (part "R-US_0204/7"))
    )
    (comp (ref "R27")
      (value "R-US_0204/7")
      (footprint "eagle-import:0204_7")
      (libsource (lib "eagle-import") (part "R-US_0204/7"))
    )
    (comp (ref "R28")
      (value "R-US_0204/7")
      (footprint "eagle-import:0204_7")
      (libsource (lib "eagle-import") (part "R-US_0204/7"))
    )
    (comp (ref "R29")
      (value "R-US_0204/7")
      (footprint "eagle-import:0204_7")
      (libsource (lib "eagle-import") (part "R-US_0204/7"))
    )
    (comp (ref "R30")
      (value "R-US_0204/7")
      (footprint "eagle-import:0204_7")
      (libsource (lib "eagle-import") (part "R-US_0204/7"))
    )
    (comp (ref "R31")
      (value "R-US_0204/7")
      (footprint "eagle-import:0204_7")
      (libsource (lib "eagle-import") (part "R-US_0204/7"))
    )
    (comp (ref "R32")
      (value "R-US_0204/7")
      (footprint "eagle-import:0204_7")
      (libsource (lib "eagle-import") (part "R-US_0204/7"))
    )
    (comp (ref "R33")
      (value "R-US_0204/7")
      (footprint "eagle-import:0204_7")
      (libsource (lib "eagle-import") (part "R-US_0204/7"))
    )
    (comp (ref "R34")
      (value "R-US_0204/7")
      (footprint "eagle-import:0204_7")
      (libsource (lib "eagle-import") (part "R-US_0204/7"))
    )
    (comp (ref "R35")
      (value "R-US_0204/7")
      (footprint "eagle-import:0204_7")
      (libsource (lib "eagle-import") (part "R-US_0204/7"))
    )
    (comp (ref "R36")
      (value "R-US_0204/7")
      (footprint "eagle-import:0204_7")
      (libsource (lib "eagle-import") (part "R-US_0204/7"))
    )
    (comp (ref "R37")
      (value "R-US_0204/7")
      (footprint "eagle-import:0204_7")
      (libsource (lib "eagle-import") (part "R-US_0204/7"))
    )
    (comp (ref "R38")
      (value "R-US_0204/7")
      (footprint "eagle-import:0204_7")
      (libsource (lib "eagle-import") (part "R-US_0204/7"))
    )
    (comp (ref "R39")
      (value "R-US_0204/7")
      (footprint "eagle-import:0204_7")
      (libsource (lib "eagle-import") (part "R-US_0204/7"))
    )
    (comp (ref "R40")
      (value "10k")
      (footprint "eagle-import:0204_7")
      (libsource (lib "eagle-import") (part "R-US_0204/7"))
    )
    (comp (ref "R41")
      (value "TRIM_US-S63P")
      (footprint "eagle-import:S63P")
      (libsource (lib "eagle-import") (part "TRIM_US-S63P"))
    )
    (comp (ref "R42")
      (value "R-US_0204/7")
      (footprint "eagle-import:0204_7")
      (libsource (lib "eagle-import") (part "R-US_0204/7"))
    )
    (comp (ref "R43")
      (value "R-US_0204/7")
      (footprint "eagle-import:0204_7")
      (libsource (lib "eagle-import") (part "R-US_0204/7"))
    )
    (comp (ref "R44")
      (value "R-US_0204/7")
      (footprint "eagle-import:0204_7")
      (libsource (lib "eagle-import") (part "R-US_0204/7"))
    )
    (comp (ref "R45")
      (value "R-US_0204/7")
      (footprint "eagle-import:0204_7")
      (libsource (lib "eagle-import") (part "R-US_0204/7"))
    )
    (comp (ref "R46")
      (value "R-US_0204/7")
      (footprint "eagle-import:0204_7")
      (libsource (lib "eagle-import") (part "R-US_0204/7"))
    )
    (comp (ref "R47")
      (value "R-US_0204/7")
      (footprint "eagle-import:0204_7")
      (libsource (lib "eagle-import") (part "R-US_0204/7"))
    )
    (comp (ref "R48")
      (value "R-US_0204/7")
      (footprint "eagle-import:0204_7")
      (libsource (lib "eagle-import") (part "R-US_0204/7"))
    )
    (comp (ref "R49")
      (value "R-US_0204/7")
      (footprint "eagle-import:0204_7")
      (libsource (lib "eagle-import") (part "R-US_0204/7"))
    )
    (comp (ref "R50")
      (value "R-US_0204/7")
      (footprint "eagle-import:0204_7")
      (libsource (lib "eagle-import") (part "R-US_0204/7"))
    )
    (comp (ref "R51")
      (value "R-US_0204/7")
      (footprint "eagle-import:0204_7")
      (libsource (lib "eagle-import") (part "R-US_0204/7"))
    )
    (comp (ref "R52")
      (value "R-US_0204/7")
      (footprint "eagle-import:0204_7")
      (libsource (lib "eagle-import") (part "R-US_0204/7"))
    )
    (comp (ref "R53")
      (value "R-US_0204/7")
      (footprint "eagle-import:0204_7")
      (libsource (lib "eagle-import") (part "R-US_0204/7"))
    )
    (comp (ref "R54")
      (value "R-US_0204/7")
      (footprint "eagle-import:0204_7")
      (libsource (lib "eagle-import") (part "R-US_0204/7"))
    )
    (comp (ref "R55")
      (value "R-US_0204/7")
      (footprint "eagle-import:0204_7")
      (libsource (lib "eagle-import") (part "R-US_0204/7"))
    )
    (comp (ref "R56")
      (value "R-US_0204/7")
      (footprint "eagle-import:0204_7")
      (libsource (lib "eagle-import") (part "R-US_0204/7"))
    )
    (comp (ref "R57")
      (value "R-US_0204/7")
      (footprint "eagle-import:0204_7")
      (libsource (lib "eagle-import") (part "R-US_0204/7"))
    )
    (comp (ref "R58")
      (value "R-US_0204/7")
      (footprint "eagle-import:0204_7")
      (libsource (lib "eagle-import") (part "R-US_0204/7"))
    )
    (comp (ref "R59")
      (value "R-US_0204/7")
      (footprint "eagle-import:0204_7")
      (libsource (lib "eagle-import") (part "R-US_0204/7"))
    )
    (comp (ref "R60")
      (value "10k")
      (footprint "eagle-import:0204_7")
      (libsource (lib "eagle-import") (part "R-US_0204/7"))
    )
    (comp (ref "R61")
      (value "1M")
      (footprint "eagle-import:S63P")
      (libsource (lib "eagle-import") (part "TRIM_US-S63P"))
    )
    (comp (ref "R65")
      (value "R-US_0204/7")
      (footprint "eagle-import:0204_7")
      (libsource (lib "eagle-import") (part "R-US_0204/7"))
    )
    (comp (ref "R66")
      (value "1k")
      (footprint "eagle-import:0204_7")
      (libsource (lib "eagle-import") (part "R-US_0204/7"))
    )
    (comp (ref "R67")
      (value "10k")
      (footprint "eagle-import:S63P")
      (libsource (lib "eagle-import") (part "TRIM_US-S63P"))
    )
    (comp (ref "S1")
      (value "MOMENTARY-SWITCH-SPST-PTH-6.0MM")
      (footprint "eagle-import:TACTILE_SWITCH_PTH_6.0MM")
      (libsource (lib "eagle-import") (part "MOMENTARY-SWITCH-SPST-PTH-6.0MM"))
    )
    (comp (ref "S2")
      (value "MOMENTARY-SWITCH-SPST-PTH-6.0MM")
      (footprint "eagle-import:TACTILE_SWITCH_PTH_6.0MM")
      (libsource (lib "eagle-import") (part "MOMENTARY-SWITCH-SPST-PTH-6.0MM"))
    )
    (comp (ref "S3")
      (value "MOMENTARY-SWITCH-SPST-PTH-6.0MM")
      (footprint "eagle-import:TACTILE_SWITCH_PTH_6.0MM")
      (libsource (lib "eagle-import") (part "MOMENTARY-SWITCH-SPST-PTH-6.0MM"))
    )
    (comp (ref "S4")
      (value "MOMENTARY-SWITCH-SPST-PTH-6.0MM")
      (footprint "eagle-import:TACTILE_SWITCH_PTH_6.0MM")
      (libsource (lib "eagle-import") (part "MOMENTARY-SWITCH-SPST-PTH-6.0MM"))
    )
    (comp (ref "S5")
      (value "MOMENTARY-SWITCH-SPST-PTH-6.0MM")
      (footprint "eagle-import:TACTILE_SWITCH_PTH_6.0MM")
      (libsource (lib "eagle-import") (part "MOMENTARY-SWITCH-SPST-PTH-6.0MM"))
    )
    (comp (ref "S6")
      (value "MOMENTARY-SWITCH-SPST-PTH-6.0MM")
      (footprint "eagle-import:TACTILE_SWITCH_PTH_6.0MM")
      (libsource (lib "eagle-import") (part "MOMENTARY-SWITCH-SPST-PTH-6.0MM"))
    )
    (comp (ref "S7")
      (value "DPDT_JS202011CQN")
      (footprint "eagle-import:DPDT_JS202011CQN")
      (libsource (lib "eagle-import") (part "DPDT_JS202011CQN"))
    )
    (comp (ref "S8")
      (value "MOMENTARY-SWITCH-SPST-PTH-6.0MM")
      (footprint "eagle-import:TACTILE_SWITCH_PTH_6.0MM")
      (libsource (lib "eagle-import") (part "MOMENTARY-SWITCH-SPST-PTH-6.0MM"))
    )
    (comp (ref "S9")
      (value "MOMENTARY-SWITCH-SPST-PTH-6.0MM")
      (footprint "eagle-import:TACTILE_SWITCH_PTH_6.0MM")
      (libsource (lib "eagle-import") (part "MOMENTARY-SWITCH-SPST-PTH-6.0MM"))
    )
    (comp (ref "S10")
      (value "DPDT_JS202011CQN")
      (footprint "eagle-import:DPDT_JS202011CQN")
      (libsource (lib "eagle-import") (part "DPDT_JS202011CQN"))
    )
    (comp (ref "S11")
      (value "MOMENTARY-SWITCH-SPST-PTH-6.0MM")
      (footprint "eagle-import:TACTILE_SWITCH_PTH_6.0MM")
      (libsource (lib "eagle-import") (part "MOMENTARY-SWITCH-SPST-PTH-6.0MM"))
    )
    (comp (ref "S12")
      (value "MOMENTARY-SWITCH-SPST-PTH-6.0MM")
      (footprint "eagle-import:TACTILE_SWITCH_PTH_6.0MM")
      (libsource (lib "eagle-import") (part "MOMENTARY-SWITCH-SPST-PTH-6.0MM"))
    )
    (comp (ref "T1")
      (value "BC547")
      (footprint "eagle-import:TO92")
      (libsource (lib "eagle-import") (part "BC547"))
    )
    (comp (ref "T2")
      (value "BC547")
      (footprint "eagle-import:TO92")
      (libsource (lib "eagle-import") (part "BC547"))
    )
    (comp (ref "T3")
      (value "BC547")
      (footprint "eagle-import:TO92")
      (libsource (lib "eagle-import") (part "BC547"))
    )
    (comp (ref "T4")
      (value "BC547")
      (footprint "eagle-import:TO92")
      (libsource (lib "eagle-import") (part "BC547"))
    )
    (comp (ref "T5")
      (value "BC547")
      (footprint "eagle-import:TO92")
      (libsource (lib "eagle-import") (part "BC547"))
    )
    (comp (ref "T6")
      (value "BC547")
      (footprint "eagle-import:TO92")
      (libsource (lib "eagle-import") (part "BC547"))
    )
    (comp (ref "T7")
      (value "BC547")
      (footprint "eagle-import:TO92")
      (libsource (lib "eagle-import") (part "BC547"))
    )
    (comp (ref "X1")
      (value "1501_03")
      (footprint "eagle-import:1501_03")
      (libsource (lib "eagle-import") (part "1501_03"))
    )
    (comp (ref "X2")
      (value "1501_03")
      (footprint "eagle-import:1501_03")
      (libsource (lib "eagle-import") (part "1501_03"))
    )
    (comp (ref "X3")
      (value "1501_03")
      (footprint "eagle-import:1501_03")
      (libsource (lib "eagle-import") (part "1501_03"))
    )
    (comp (ref "X4")
      (value "1501_03")
      (footprint "eagle-import:1501_03")
      (libsource (lib "eagle-import") (part "1501_03"))
    )
  )
  (nets
    (net (code "1") (name "5V") (class "Default")
      (node (ref "IC1") (pin "8") (pinfunction "V+_8") (pintype "power_in"))
      (node (ref "IC10") (pin "10") (pinfunction "KA_10") (pintype "bidirectional"))
      (node (ref "IC10") (pin "16") (pinfunction "VDD_16") (pintype "bidirectional"))
      (node (ref "IC11") (pin "4") (pinfunction "VCC_4") (pintype "power_in"))
      (node (ref "IC12") (pin "16") (pinfunction "VDD_16") (pintype "bidirectional"))
      (node (ref "IC12") (pin "9") (pinfunction "KC_9") (pintype "bidirectional"))
      (node (ref "IC13") (pin "16") (pinfunction "VDD_16") (pintype "bidirectional"))
      (node (ref "IC14") (pin "4") (pinfunction "/RES_4") (pintype "input"))
      (node (ref "IC14") (pin "8") (pinfunction "VCC+_8") (pintype "power_in"))
      (node (ref "IC16") (pin "4") (pinfunction "/RES_4") (pintype "input"))
      (node (ref "IC16") (pin "8") (pinfunction "VCC+_8") (pintype "power_in"))
      (node (ref "IC2") (pin "8") (pinfunction "V+_8") (pintype "power_in"))
      (node (ref "IC3") (pin "8") (pinfunction "V+_8") (pintype "power_in"))
      (node (ref "IC4") (pin "8") (pinfunction "V+_8") (pintype "power_in"))
      (node (ref "IC5") (pin "8") (pinfunction "V+_8") (pintype "power_in"))
      (node (ref "IC6") (pin "8") (pinfunction "V+_8") (pintype "power_in"))
      (node (ref "IC7") (pin "8") (pinfunction "V+_8") (pintype "power_in"))
      (node (ref "IC8") (pin "8") (pinfunction "V+_8") (pintype "power_in"))
      (node (ref "IC9") (pin "8") (pinfunction "V+_8") (pintype "power_in"))
      (node (ref "LDR1") (pin "1") (pinfunction "1_1") (pintype "passive"))
      (node (ref "R1") (pin "E") (pinfunction "E_E") (pintype "passive"))
      (node (ref "R10") (pin "2") (pinfunction "2_2") (pintype "passive"))
      (node (ref "R13") (pin "E") (pinfunction "E_E") (pintype "passive"))
      (node (ref "R13") (pin "S") (pinfunction "S_S") (pintype "passive"))
      (node (ref "R14") (pin "2") (pinfunction "2_2") (pintype "passive"))
      (node (ref "R15") (pin "2") (pinfunction "2_2") (pintype "passive"))
      (node (ref "R16") (pin "2") (pinfunction "2_2") (pintype "passive"))
      (node (ref "R17") (pin "2") (pinfunction "2_2") (pintype "passive"))
      (node (ref "R18") (pin "2") (pinfunction "2_2") (pintype "passive"))
      (node (ref "R19") (pin "2") (pinfunction "2_2") (pintype "passive"))
      (node (ref "R20") (pin "2") (pinfunction "2_2") (pintype "passive"))
      (node (ref "R21") (pin "2") (pinfunction "2_2") (pintype "passive"))
      (node (ref "R22") (pin "2") (pinfunction "2_2") (pintype "passive"))
      (node (ref "R23") (pin "2") (pinfunction "2_2") (pintype "passive"))
      (node (ref "R24") (pin "2") (pinfunction "2_2") (pintype "passive"))
      (node (ref "R25") (pin "2") (pinfunction "2_2") (pintype "passive"))
      (node (ref "R41") (pin "E") (pinfunction "E_E") (pintype "passive"))
      (node (ref "R5") (pin "2") (pinfunction "2_2") (pintype "passive"))
      (node (ref "R60") (pin "2") (pinfunction "2_2") (pintype "passive"))
      (node (ref "R61") (pin "E") (pinfunction "E_E") (pintype "passive"))
      (node (ref "R66") (pin "2") (pinfunction "2_2") (pintype "passive"))
      (node (ref "R7") (pin "1") (pinfunction "1_1") (pintype "passive"))
      (node (ref "R8") (pin "1") (pinfunction "1_1") (pintype "passive"))
      (node (ref "R9") (pin "1") (pinfunction "1_1") (pintype "passive"))
      (node (ref "S1") (pin "3") (pinfunction "2_3") (pintype "passive"))
      (node (ref "S10") (pin "2") (pinfunction "LC_2") (pintype "passive"))
      (node (ref "S11") (pin "3") (pinfunction "2_3") (pintype "passive"))
      (node (ref "S3") (pin "3") (pinfunction "2_3") (pintype "passive"))
      (node (ref "S4") (pin "3") (pinfunction "2_3") (pintype "passive"))
      (node (ref "S5") (pin "3") (pinfunction "2_3") (pintype "passive"))
      (node (ref "S6") (pin "3") (pinfunction "2_3") (pintype "passive"))
      (node (ref "S7") (pin "5") (pinfunction "RC_5") (pintype "passive"))
      (node (ref "S8") (pin "3") (pinfunction "2_3") (pintype "passive"))
      (node (ref "S9") (pin "3") (pinfunction "2_3") (pintype "passive"))
    )
    (net (code "2") (name "CLK") (class "Default")
      (node (ref "IC11") (pin "1") (pinfunction "CLK_1") (pintype "input"))
      (node (ref "R51") (pin "2") (pinfunction "2_2") (pintype "passive"))
      (node (ref "S6") (pin "1") (pinfunction "1_1") (pintype "passive"))
    )
    (net (code "3") (name "GND") (class "Default")
      (node (ref "C10") (pin "2") (pinfunction "2_2") (pintype "passive"))
      (node (ref "C11") (pin "2") (pinfunction "2_2") (pintype "passive"))
      (node (ref "C14") (pin "-") (pinfunction "-_-") (pintype "passive"))
      (node (ref "C15") (pin "2") (pinfunction "2_2") (pintype "passive"))
      (node (ref "C18") (pin "-") (pinfunction "-_-") (pintype "passive"))
      (node (ref "C19") (pin "2") (pinfunction "2_2") (pintype "passive"))
      (node (ref "IC1") (pin "3") (pinfunction "+IN_3") (pintype "input"))
      (node (ref "IC1") (pin "4") (pinfunction "V-_4") (pintype "power_in"))
      (node (ref "IC10") (pin "15") (pinfunction "EXPAND_15") (pintype "bidirectional"))
      (node (ref "IC10") (pin "2") (pinfunction "KD_2") (pintype "bidirectional"))
      (node (ref "IC10") (pin "7") (pinfunction "KB_7") (pintype "bidirectional"))
      (node (ref "IC10") (pin "8") (pinfunction "VSS_8") (pintype "bidirectional"))
      (node (ref "IC10") (pin "9") (pinfunction "KC_9") (pintype "bidirectional"))
      (node (ref "IC11") (pin "11") (pinfunction "GND_11") (pintype "power_in"))
      (node (ref "IC12") (pin "10") (pinfunction "KA_10") (pintype "bidirectional"))
      (node (ref "IC12") (pin "15") (pinfunction "EXPAND_15") (pintype "bidirectional"))
      (node (ref "IC12") (pin "2") (pinfunction "KD_2") (pintype "bidirectional"))
      (node (ref "IC12") (pin "7") (pinfunction "KB_7") (pintype "bidirectional"))
      (node (ref "IC12") (pin "8") (pinfunction "VSS_8") (pintype "bidirectional"))
      (node (ref "IC13") (pin "10") (pinfunction "KA_10") (pintype "bidirectional"))
      (node (ref "IC13") (pin "15") (pinfunction "EXPAND_15") (pintype "bidirectional"))
      (node (ref "IC13") (pin "2") (pinfunction "KD_2") (pintype "bidirectional"))
      (node (ref "IC13") (pin "7") (pinfunction "KB_7") (pintype "bidirectional"))
      (node (ref "IC13") (pin "8") (pinfunction "VSS_8") (pintype "bidirectional"))
      (node (ref "IC13") (pin "9") (pinfunction "KC_9") (pintype "bidirectional"))
      (node (ref "IC14") (pin "1") (pinfunction "GND_1") (pintype "power_in"))
      (node (ref "IC16") (pin "1") (pinfunction "GND_1") (pintype "power_in"))
      (node (ref "IC2") (pin "4") (pinfunction "V-_4") (pintype "power_in"))
      (node (ref "IC3") (pin "3") (pinfunction "+IN_3") (pintype "input"))
      (node (ref "IC3") (pin "4") (pinfunction "V-_4") (pintype "power_in"))
      (node (ref "IC4") (pin "4") (pinfunction "V-_4") (pintype "power_in"))
      (node (ref "IC5") (pin "3") (pinfunction "+IN_3") (pintype "input"))
      (node (ref "IC5") (pin "4") (pinfunction "V-_4") (pintype "power_in"))
      (node (ref "IC6") (pin "3") (pinfunction "+IN_3") (pintype "input"))
      (node (ref "IC6") (pin "4") (pinfunction "V-_4") (pintype "power_in"))
      (node (ref "IC7") (pin "4") (pinfunction "V-_4") (pintype "power_in"))
      (node (ref "IC8") (pin "4") (pinfunction "V-_4") (pintype "power_in"))
      (node (ref "IC9") (pin "4") (pinfunction "V-_4") (pintype "power_in"))
      (node (ref "J1") (pin "1") (pinfunction "1_1") (pintype "passive"))
      (node (ref "J10") (pin "1") (pinfunction "1_1") (pintype "passive"))
      (node (ref "J11") (pin "1") (pinfunction "1_1") (pintype "passive"))
      (node (ref "J12") (pin "2") (pinfunction "2_2") (pintype "passive"))
      (node (ref "J13") (pin "1") (pinfunction "1_1") (pintype "passive"))
      (node (ref "J14") (pin "2") (pinfunction "2_2") (pintype "passive"))
      (node (ref "J2") (pin "2") (pinfunction "2_2") (pintype "passive"))
      (node (ref "J3") (pin "1") (pinfunction "1_1") (pintype "passive"))
      (node (ref "J4") (pin "2") (pinfunction "2_2") (pintype "passive"))
      (node (ref "J5") (pin "2") (pinfunction "2_2") (pintype "passive"))
      (node (ref "J6") (pin "2") (pinfunction "2_2") (pintype "passive"))
      (node (ref "J8") (pin "1") (pinfunction "1_1") (pintype "passive"))
      (node (ref "LDR") (pin "2") (pinfunction "2_2") (pintype "passive"))
      (node (ref "LED1") (pin "K") (pinfunction "C_K") (pintype "passive"))
      (node (ref "LED14") (pin "K") (pinfunction "C_K") (pintype "passive"))
      (node (ref "LED15") (pin "K") (pinfunction "C_K") (pintype "passive"))
      (node (ref "LED16") (pin "K") (pinfunction "C_K") (pintype "passive"))
      (node (ref "LED17") (pin "K") (pinfunction "C_K") (pintype "passive"))
      (node (ref "LED18") (pin "K") (pinfunction "C_K") (pintype "passive"))
      (node (ref "LED19") (pin "K") (pinfunction "C_K") (pintype "passive"))
      (node (ref "LED20") (pin "K") (pinfunction "C_K") (pintype "passive"))
      (node (ref "LED21") (pin "K") (pinfunction "C_K") (pintype "passive"))
      (node (ref "LED22") (pin "K") (pinfunction "C_K") (pintype "passive"))
      (node (ref "LED23") (pin "K") (pinfunction "C_K") (pintype "passive"))
      (node (ref "LED24") (pin "K") (pinfunction "C_K") (pintype "passive"))
      (node (ref "LED25") (pin "K") (pinfunction "C_K") (pintype "passive"))
      (node (ref "LED26") (pin "K") (pinfunction "C_K") (pintype "passive"))
      (node (ref "LED27") (pin "K") (pinfunction "C_K") (pintype "passive"))
      (node (ref "LED29") (pin "K") (pinfunction "C_K") (pintype "passive"))
      (node (ref "LED3") (pin "K") (pinfunction "C_K") (pintype "passive"))
      (node (ref "LED4") (pin "K") (pinfunction "C_K") (pintype "passive"))
      (node (ref "R1") (pin "A") (pinfunction "A_A") (pintype "passive"))
      (node (ref "R29") (pin "2") (pinfunction "2_2") (pintype "passive"))
      (node (ref "R3") (pin "1") (pinfunction "1_1") (pintype "passive"))
      (node (ref "R37") (pin "2") (pinfunction "2_2") (pintype "passive"))
      (node (ref "R4") (pin "1") (pinfunction "1_1") (pintype "passive"))
      (node (ref "R40") (pin "2") (pinfunction "2_2") (pintype "passive"))
      (node (ref "R41") (pin "A") (pinfunction "A_A") (pintype "passive"))
      (node (ref "R45") (pin "1") (pinfunction "1_1") (pintype "passive"))
      (node (ref "R46") (pin "1") (pinfunction "1_1") (pintype "passive"))
      (node (ref "S12") (pin "1") (pinfunction "1_1") (pintype "passive"))
      (node (ref "T1") (pin "1") (pinfunction "E_1") (pintype "passive"))
      (node (ref "T2") (pin "1") (pinfunction "E_1") (pintype "passive"))
      (node (ref "T3") (pin "1") (pinfunction "E_1") (pintype "passive"))
      (node (ref "T4") (pin "1") (pinfunction "E_1") (pintype "passive"))
      (node (ref "T5") (pin "1") (pinfunction "E_1") (pintype "passive"))
      (node (ref "T6") (pin "1") (pinfunction "E_1") (pintype "passive"))
      (node (ref "T7") (pin "1") (pinfunction "E_1") (pintype "passive"))
      (node (ref "X1") (pin "1") (pinfunction "1_1") (pintype "passive"))
      (node (ref "X2") (pin "1") (pinfunction "1_1") (pintype "passive"))
      (node (ref "X3") (pin "1") (pinfunction "1_1") (pintype "passive"))
      (node (ref "X4") (pin "1") (pinfunction "1_1") (pintype "passive"))
    )
    (net (code "4") (name "IN") (class "Default")
      (node (ref "IC13") (pin "11") (pinfunction "INPUTS_D_11") (pintype "bidirectional"))
      (node (ref "IC13") (pin "12") (pinfunction "INPUTS_C_12") (pintype "bidirectional"))
      (node (ref "IC13") (pin "13") (pinfunction "INPUTS_B_13") (pintype "bidirectional"))
      (node (ref "IC13") (pin "14") (pinfunction "INPUTS_A_14") (pintype "bidirectional"))
      (node (ref "IC13") (pin "3") (pinfunction "INPUTS_H_3") (pintype "bidirectional"))
      (node (ref "IC13") (pin "4") (pinfunction "INPUTS_G_4") (pintype "bidirectional"))
      (node (ref "IC13") (pin "5") (pinfunction "INPUTS_F_5") (pintype "bidirectional"))
      (node (ref "IC13") (pin "6") (pinfunction "INPUTS_E_6") (pintype "bidirectional"))
      (node (ref "R58") (pin "2") (pinfunction "2_2") (pintype "passive"))
      (node (ref "S11") (pin "1") (pinfunction "1_1") (pintype "passive"))
    )
    (net (code "5") (name "IN1") (class "Default")
      (node (ref "IC10") (pin "3") (pinfunction "INPUTS_H_3") (pintype "bidirectional"))
      (node (ref "IC10") (pin "4") (pinfunction "INPUTS_G_4") (pintype "bidirectional"))
      (node (ref "IC10") (pin "5") (pinfunction "INPUTS_F_5") (pintype "bidirectional"))
      (node (ref "IC10") (pin "6") (pinfunction "INPUTS_E_6") (pintype "bidirectional"))
      (node (ref "IC12") (pin "3") (pinfunction "INPUTS_H_3") (pintype "bidirectional"))
      (node (ref "IC12") (pin "4") (pinfunction "INPUTS_G_4") (pintype "bidirectional"))
      (node (ref "IC12") (pin "5") (pinfunction "INPUTS_F_5") (pintype "bidirectional"))
      (node (ref "IC12") (pin "6") (pinfunction "INPUTS_E_6") (pintype "bidirectional"))
      (node (ref "R48") (pin "2") (pinfunction "2_2") (pintype "passive"))
      (node (ref "R54") (pin "2") (pinfunction "2_2") (pintype "passive"))
      (node (ref "S4") (pin "1") (pinfunction "1_1") (pintype "passive"))
      (node (ref "S8") (pin "1") (pinfunction "1_1") (pintype "passive"))
    )
    (net (code "6") (name "IN2") (class "Default")
      (node (ref "IC10") (pin "11") (pinfunction "INPUTS_D_11") (pintype "bidirectional"))
      (node (ref "IC10") (pin "12") (pinfunction "INPUTS_C_12") (pintype "bidirectional"))
      (node (ref "IC10") (pin "13") (pinfunction "INPUTS_B_13") (pintype "bidirectional"))
      (node (ref "IC10") (pin "14") (pinfunction "INPUTS_A_14") (pintype "bidirectional"))
      (node (ref "IC12") (pin "11") (pinfunction "INPUTS_D_11") (pintype "bidirectional"))
      (node (ref "IC12") (pin "12") (pinfunction "INPUTS_C_12") (pintype "bidirectional"))
      (node (ref "IC12") (pin "13") (pinfunction "INPUTS_B_13") (pintype "bidirectional"))
      (node (ref "IC12") (pin "14") (pinfunction "INPUTS_A_14") (pintype "bidirectional"))
      (node (ref "R49") (pin "2") (pinfunction "2_2") (pintype "passive"))
      (node (ref "R55") (pin "2") (pinfunction "2_2") (pintype "passive"))
      (node (ref "S5") (pin "1") (pinfunction "1_1") (pintype "passive"))
      (node (ref "S9") (pin "1") (pinfunction "1_1") (pintype "passive"))
    )
    (net (code "7") (name "J") (class "Default")
      (node (ref "IC11") (pin "14") (pinfunction "J_14") (pintype "input"))
      (node (ref "R52") (pin "2") (pinfunction "2_2") (pintype "passive"))
      (node (ref "S7") (pin "6") (pinfunction "R2_6") (pintype "passive"))
    )
    (net (code "8") (name "K") (class "Default")
      (node (ref "IC11") (pin "3") (pinfunction "K_3") (pintype "input"))
      (node (ref "R57") (pin "2") (pinfunction "2_2") (pintype "passive"))
      (node (ref "S10") (pin "3") (pinfunction "L2_3") (pintype "passive"))
    )
    (net (code "9") (name "Net-(C9-Pad1)") (class "Default")
      (node (ref "C9") (pin "1") (pinfunction "1_1") (pintype "passive"))
      (node (ref "J13") (pin "2") (pinfunction "2_2") (pintype "passive"))
    )
    (net (code "10") (name "Net-(C12-Pad1)") (class "Default")
      (node (ref "C12") (pin "1") (pinfunction "1_1") (pintype "passive"))
      (node (ref "X4") (pin "2") (pinfunction "2_2") (pintype "passive"))
    )
    (net (code "11") (name "Net-(C13-Pad1)") (class "Default")
      (node (ref "C13") (pin "1") (pinfunction "1_1") (pintype "passive"))
      (node (ref "X4") (pin "3") (pinfunction "3_3") (pintype "passive"))
    )
    (net (code "12") (name "Net-(IC1A--IN)") (class "Default")
      (node (ref "IC1") (pin "2") (pinfunction "-IN_2") (pintype "input"))
      (node (ref "R26") (pin "2") (pinfunction "2_2") (pintype "passive"))
      (node (ref "R27") (pin "1") (pinfunction "1_1") (pintype "passive"))
    )
    (net (code "13") (name "Net-(IC1A-OUT)") (class "Default")
      (node (ref "IC1") (pin "1") (pinfunction "OUT_1") (pintype "output"))
      (node (ref "J2") (pin "1") (pinfunction "1_1") (pintype "passive"))
      (node (ref "R26") (pin "1") (pinfunction "1_1") (pintype "passive"))
    )
    (net (code "14") (name "Net-(IC2A-+IN)") (class "Default")
      (node (ref "IC2") (pin "3") (pinfunction "+IN_3") (pintype "input"))
      (node (ref "J3") (pin "2") (pinfunction "2_2") (pintype "passive"))
    )
    (net (code "15") (name "Net-(IC2A--IN)") (class "Default")
      (node (ref "IC2") (pin "2") (pinfunction "-IN_2") (pintype "input"))
      (node (ref "R28") (pin "2") (pinfunction "2_2") (pintype "passive"))
      (node (ref "R29") (pin "1") (pinfunction "1_1") (pintype "passive"))
    )
    (net (code "16") (name "Net-(IC2A-OUT)") (class "Default")
      (node (ref "IC2") (pin "1") (pinfunction "OUT_1") (pintype "output"))
      (node (ref "J4") (pin "1") (pinfunction "1_1") (pintype "passive"))
      (node (ref "R28") (pin "1") (pinfunction "1_1") (pintype "passive"))
    )
    (net (code "17") (name "Net-(IC3A--IN)") (class "Default")
      (node (ref "IC3") (pin "2") (pinfunction "-IN_2") (pintype "input"))
      (node (ref "R30") (pin "2") (pinfunction "2_2") (pintype "passive"))
      (node (ref "R31") (pin "1") (pinfunction "1_1") (pintype "passive"))
      (node (ref "R32") (pin "1") (pinfunction "1_1") (pintype "passive"))
      (node (ref "R33") (pin "1") (pinfunction "1_1") (pintype "passive"))
    )
    (net (code "18") (name "Net-(IC3A-OUT)") (class "Default")
      (node (ref "IC3") (pin "1") (pinfunction "OUT_1") (pintype "output"))
      (node (ref "J6") (pin "1") (pinfunction "1_1") (pintype "passive"))
      (node (ref "R30") (pin "1") (pinfunction "1_1") (pintype "passive"))
    )
    (net (code "19") (name "Net-(IC4A-+IN)") (class "Default")
      (node (ref "IC4") (pin "3") (pinfunction "+IN_3") (pintype "input"))
      (node (ref "R36") (pin "1") (pinfunction "1_1") (pintype "passive"))
      (node (ref "R37") (pin "1") (pinfunction "1_1") (pintype "passive"))
    )
    (net (code "20") (name "Net-(IC4A--IN)") (class "Default")
      (node (ref "IC4") (pin "2") (pinfunction "-IN_2") (pintype "input"))
      (node (ref "R34") (pin "2") (pinfunction "2_2") (pintype "passive"))
      (node (ref "R35") (pin "1") (pinfunction "1_1") (pintype "passive"))
    )
    (net (code "21") (name "Net-(IC4A-OUT)") (class "Default")
      (node (ref "IC4") (pin "1") (pinfunction "OUT_1") (pintype "output"))
      (node (ref "J5") (pin "1") (pinfunction "1_1") (pintype "passive"))
      (node (ref "R34") (pin "1") (pinfunction "1_1") (pintype "passive"))
    )
    (net (code "22") (name "Net-(IC5A--IN)") (class "Default")
      (node (ref "C8") (pin "1") (pinfunction "1_1") (pintype "passive"))
      (node (ref "IC5") (pin "2") (pinfunction "-IN_2") (pintype "input"))
      (node (ref "R39") (pin "1") (pinfunction "1_1") (pintype "passive"))
    )
    (net (code "23") (name "Net-(IC5A-OUT)") (class "Default")
      (node (ref "C8") (pin "2") (pinfunction "2_2") (pintype "passive"))
      (node (ref "IC5") (pin "1") (pinfunction "OUT_1") (pintype "output"))
      (node (ref "J12") (pin "1") (pinfunction "1_1") (pintype "passive"))
    )
    (net (code "24") (name "Net-(IC6A--IN)") (class "Default")
      (node (ref "C9") (pin "2") (pinfunction "2_2") (pintype "passive"))
      (node (ref "IC6") (pin "2") (pinfunction "-IN_2") (pintype "input"))
      (node (ref "R38") (pin "2") (pinfunction "2_2") (pintype "passive"))
    )
    (net (code "25") (name "Net-(IC6A-OUT)") (class "Default")
      (node (ref "IC6") (pin "1") (pinfunction "OUT_1") (pintype "output"))
      (node (ref "J14") (pin "1") (pinfunction "1_1") (pintype "passive"))
      (node (ref "R38") (pin "1") (pinfunction "1_1") (pintype "passive"))
    )
    (net (code "26") (name "Net-(IC7A-+IN)") (class "Default")
      (node (ref "IC7") (pin "3") (pinfunction "+IN_3") (pintype "input"))
      (node (ref "LDR1") (pin "2") (pinfunction "2_2") (pintype "passive"))
      (node (ref "R40") (pin "1") (pinfunction "1_1") (pintype "passive"))
    )
    (net (code "27") (name "Net-(IC7A--IN)") (class "Default")
      (node (ref "IC7") (pin "2") (pinfunction "-IN_2") (pintype "input"))
      (node (ref "R41") (pin "S") (pinfunction "S_S") (pintype "passive"))
    )
    (net (code "28") (name "Net-(IC7A-OUT)") (class "Default")
      (node (ref "IC7") (pin "1") (pinfunction "OUT_1") (pintype "output"))
      (node (ref "R42") (pin "2") (pinfunction "2_2") (pintype "passive"))
    )
    (net (code "29") (name "Net-(IC8A-+IN)") (class "Default")
      (node (ref "C10") (pin "1") (pinfunction "1_1") (pintype "passive"))
      (node (ref "IC8") (pin "3") (pinfunction "+IN_3") (pintype "input"))
      (node (ref "R44") (pin "2") (pinfunction "2_2") (pintype "passive"))
    )
    (net (code "30") (name "Net-(IC8A--IN)") (class "Default")
      (node (ref "IC8") (pin "1") (pinfunction "OUT_1") (pintype "output"))
      (node (ref "IC8") (pin "2") (pinfunction "-IN_2") (pintype "input"))
      (node (ref "X1") (pin "3") (pinfunction "3_3") (pintype "passive"))
    )
    (net (code "31") (name "Net-(IC8B-+IN)") (class "Default")
      (node (ref "C11") (pin "1") (pinfunction "1_1") (pintype "passive"))
      (node (ref "IC8") (pin "5") (pinfunction "+IN_5") (pintype "input"))
      (node (ref "R43") (pin "2") (pinfunction "2_2") (pintype "passive"))
    )
    (net (code "32") (name "Net-(IC8B--IN)") (class "Default")
      (node (ref "IC8") (pin "6") (pinfunction "-IN_6") (pintype "input"))
      (node (ref "IC8") (pin "7") (pinfunction "OUT_7") (pintype "output"))
      (node (ref "X1") (pin "2") (pinfunction "2_2") (pintype "passive"))
    )
    (net (code "33") (name "Net-(IC9A-+IN)") (class "Default")
      (node (ref "C13") (pin "2") (pinfunction "2_2") (pintype "passive"))
      (node (ref "IC9") (pin "3") (pinfunction "+IN_3") (pintype "input"))
      (node (ref "R45") (pin "2") (pinfunction "2_2") (pintype "passive"))
    )
    (net (code "34") (name "Net-(IC9A--IN)") (class "Default")
      (node (ref "IC9") (pin "1") (pinfunction "OUT_1") (pintype "output"))
      (node (ref "IC9") (pin "2") (pinfunction "-IN_2") (pintype "input"))
      (node (ref "X3") (pin "3") (pinfunction "3_3") (pintype "passive"))
    )
    (net (code "35") (name "Net-(IC9B-+IN)") (class "Default")
      (node (ref "C12") (pin "2") (pinfunction "2_2") (pintype "passive"))
      (node (ref "IC9") (pin "5") (pinfunction "+IN_5") (pintype "input"))
      (node (ref "R46") (pin "2") (pinfunction "2_2") (pintype "passive"))
    )
    (net (code "36") (name "Net-(IC9B--IN)") (class "Default")
      (node (ref "IC9") (pin "6") (pinfunction "-IN_6") (pintype "input"))
      (node (ref "IC9") (pin "7") (pinfunction "OUT_7") (pintype "output"))
      (node (ref "X3") (pin "2") (pinfunction "2_2") (pintype "passive"))
    )
    (net (code "37") (name "Net-(IC14-CON)") (class "Default")
      (node (ref "C15") (pin "1") (pinfunction "1_1") (pintype "passive"))
      (node (ref "IC14") (pin "5") (pinfunction "CON_5") (pintype "input"))
    )
    (net (code "38") (name "Net-(IC14-DIS)") (class "Default")
      (node (ref "C14") (pin "+") (pinfunction "+_+") (pintype "passive"))
      (node (ref "IC14") (pin "6") (pinfunction "TRE_6") (pintype "input"))
      (node (ref "IC14") (pin "7") (pinfunction "DIS_7") (pintype "input"))
      (node (ref "R61") (pin "A") (pinfunction "A_A") (pintype "passive"))
      (node (ref "R61") (pin "S") (pinfunction "S_S") (pintype "passive"))
    )
    (net (code "39") (name "Net-(IC14-OUT)") (class "Default")
      (node (ref "IC14") (pin "3") (pinfunction "OUT_3") (pintype "output"))
      (node (ref "R59") (pin "2") (pinfunction "2_2") (pintype "passive"))
    )
    (net (code "40") (name "Net-(IC16-CON)") (class "Default")
      (node (ref "C19") (pin "1") (pinfunction "1_1") (pintype "passive"))
      (node (ref "IC16") (pin "5") (pinfunction "CON_5") (pintype "input"))
    )
    (net (code "41") (name "Net-(IC16-DIS)") (class "Default")
      (node (ref "IC16") (pin "7") (pinfunction "DIS_7") (pintype "input"))
      (node (ref "R66") (pin "1") (pinfunction "1_1") (pintype "passive"))
      (node (ref "R67") (pin "E") (pinfunction "E_E") (pintype "passive"))
    )
    (net (code "42") (name "Net-(IC16-OUT)") (class "Default")
      (node (ref "IC16") (pin "3") (pinfunction "OUT_3") (pintype "output"))
      (node (ref "R65") (pin "2") (pinfunction "2_2") (pintype "passive"))
    )
    (net (code "43") (name "Net-(J1-Pad2)") (class "Default")
      (node (ref "J1") (pin "2") (pinfunction "2_2") (pintype "passive"))
      (node (ref "R27") (pin "2") (pinfunction "2_2") (pintype "passive"))
    )
    (net (code "44") (name "Net-(J7-Pad1)") (class "Default")
      (node (ref "J7") (pin "1") (pinfunction "1_1") (pintype "passive"))
      (node (ref "R33") (pin "2") (pinfunction "2_2") (pintype "passive"))
    )
    (net (code "45") (name "Net-(J7-Pad2)") (class "Default")
      (node (ref "J7") (pin "2") (pinfunction "2_2") (pintype "passive"))
      (node (ref "R31") (pin "2") (pinfunction "2_2") (pintype "passive"))
    )
    (net (code "46") (name "Net-(J7-Pad3)") (class "Default")
      (node (ref "J7") (pin "3") (pinfunction "3_3") (pintype "passive"))
      (node (ref "R32") (pin "2") (pinfunction "2_2") (pintype "passive"))
    )
    (net (code "47") (name "Net-(J9-Pad1)") (class "Default")
      (node (ref "J9") (pin "1") (pinfunction "1_1") (pintype "passive"))
      (node (ref "R36") (pin "2") (pinfunction "2_2") (pintype "passive"))
    )
    (net (code "48") (name "Net-(J9-Pad2)") (class "Default")
      (node (ref "J9") (pin "2") (pinfunction "2_2") (pintype "passive"))
      (node (ref "R35") (pin "2") (pinfunction "2_2") (pintype "passive"))
    )
    (net (code "49") (name "Net-(J11-Pad2)") (class "Default")
      (node (ref "J11") (pin "2") (pinfunction "2_2") (pintype "passive"))
      (node (ref "R39") (pin "2") (pinfunction "2_2") (pintype "passive"))
    )
    (net (code "50") (name "Net-(LDR-Pad1)") (class "Default")
      (node (ref "LDR") (pin "1") (pinfunction "1_1") (pintype "passive"))
      (node (ref "R13") (pin "A") (pinfunction "A_A") (pintype "passive"))
      (node (ref "R6") (pin "2") (pinfunction "2_2") (pintype "passive"))
    )
    (net (code "51") (name "Net-(LED1-PadA)") (class "Default")
      (node (ref "LED1") (pin "A") (pinfunction "A_A") (pintype "passive"))
      (node (ref "R2") (pin "1") (pinfunction "1_1") (pintype "passive"))
    )
    (net (code "52") (name "Net-(LED2-C)") (class "Default")
      (node (ref "C1") (pin "-") (pinfunction "-_-") (pintype "passive"))
      (node (ref "LED2") (pin "K") (pinfunction "C_K") (pintype "passive"))
      (node (ref "R4") (pin "2") (pinfunction "2_2") (pintype "passive"))
    )
    (net (code "53") (name "Net-(LED2-PadA)") (class "Default")
      (node (ref "LED2") (pin "A") (pinfunction "A_A") (pintype "passive"))
      (node (ref "S2") (pin "1") (pinfunction "1_1") (pintype "passive"))
    )
    (net (code "54") (name "Net-(LED3-PadA)") (class "Default")
      (node (ref "LED3") (pin "A") (pinfunction "A_A") (pintype "passive"))
      (node (ref "R7") (pin "2") (pinfunction "2_2") (pintype "passive"))
      (node (ref "R8") (pin "2") (pinfunction "2_2") (pintype "passive"))
      (node (ref "R9") (pin "2") (pinfunction "2_2") (pintype "passive"))
    )
    (net (code "55") (name "Net-(LED4-PadA)") (class "Default")
      (node (ref "LED4") (pin "A") (pinfunction "A_A") (pintype "passive"))
      (node (ref "R12") (pin "1") (pinfunction "1_1") (pintype "passive"))
    )
    (net (code "56") (name "Net-(LED5-C)") (class "Default")
      (node (ref "L1") (pin "2") (pinfunction "2_2") (pintype "passive"))
      (node (ref "LED5") (pin "K") (pinfunction "C_K") (pintype "passive"))
      (node (ref "LED6") (pin "A") (pinfunction "A_A") (pintype "passive"))
      (node (ref "R3") (pin "2") (pinfunction "2_2") (pintype "passive"))
    )
    (net (code "57") (name "Net-(LED6-C)") (class "Default")
      (node (ref "L1") (pin "1") (pinfunction "1_1") (pintype "passive"))
      (node (ref "LED5") (pin "A") (pinfunction "A_A") (pintype "passive"))
      (node (ref "LED6") (pin "K") (pinfunction "C_K") (pintype "passive"))
      (node (ref "S3") (pin "1") (pinfunction "1_1") (pintype "passive"))
    )
    (net (code "58") (name "Net-(LED7-C)") (class "Default")
      (node (ref "LED7") (pin "K") (pinfunction "C_K") (pintype "passive"))
      (node (ref "T1") (pin "3") (pinfunction "C_3") (pintype "passive"))
    )
    (net (code "59") (name "Net-(LED7-PadA)") (class "Default")
      (node (ref "LED7") (pin "A") (pinfunction "A_A") (pintype "passive"))
      (node (ref "R5") (pin "1") (pinfunction "1_1") (pintype "passive"))
    )
    (net (code "60") (name "Net-(LED8-C)") (class "Default")
      (node (ref "C2") (pin "+") (pinfunction "+_+") (pintype "passive"))
      (node (ref "LED8") (pin "K") (pinfunction "C_K") (pintype "passive"))
      (node (ref "T2") (pin "3") (pinfunction "C_3") (pintype "passive"))
    )
    (net (code "61") (name "Net-(LED8-PadA)") (class "Default")
      (node (ref "LED8") (pin "A") (pinfunction "A_A") (pintype "passive"))
      (node (ref "R14") (pin "1") (pinfunction "1_1") (pintype "passive"))
    )
    (net (code "62") (name "Net-(LED9-C)") (class "Default")
      (node (ref "C3") (pin "+") (pinfunction "+_+") (pintype "passive"))
      (node (ref "LED9") (pin "K") (pinfunction "C_K") (pintype "passive"))
      (node (ref "T3") (pin "3") (pinfunction "C_3") (pintype "passive"))
    )
    (net (code "63") (name "Net-(LED9-PadA)") (class "Default")
      (node (ref "LED9") (pin "A") (pinfunction "A_A") (pintype "passive"))
      (node (ref "R16") (pin "1") (pinfunction "1_1") (pintype "passive"))
    )
    (net (code "64") (name "Net-(LED10-C)") (class "Default")
      (node (ref "C4") (pin "+") (pinfunction "+_+") (pintype "passive"))
      (node (ref "LED10") (pin "K") (pinfunction "C_K") (pintype "passive"))
      (node (ref "T4") (pin "3") (pinfunction "C_3") (pintype "passive"))
    )
    (net (code "65") (name "Net-(LED10-PadA)") (class "Default")
      (node (ref "LED10") (pin "A") (pinfunction "A_A") (pintype "passive"))
      (node (ref "R18") (pin "1") (pinfunction "1_1") (pintype "passive"))
    )
    (net (code "66") (name "Net-(LED11-C)") (class "Default")
      (node (ref "C5") (pin "+") (pinfunction "+_+") (pintype "passive"))
      (node (ref "LED11") (pin "K") (pinfunction "C_K") (pintype "passive"))
      (node (ref "T5") (pin "3") (pinfunction "C_3") (pintype "passive"))
    )
    (net (code "67") (name "Net-(LED11-PadA)") (class "Default")
      (node (ref "LED11") (pin "A") (pinfunction "A_A") (pintype "passive"))
      (node (ref "R20") (pin "1") (pinfunction "1_1") (pintype "passive"))
    )
    (net (code "68") (name "Net-(LED12-C)") (class "Default")
      (node (ref "C6") (pin "+") (pinfunction "+_+") (pintype "passive"))
      (node (ref "LED12") (pin "K") (pinfunction "C_K") (pintype "passive"))
      (node (ref "T6") (pin "3") (pinfunction "C_3") (pintype "passive"))
    )
    (net (code "69") (name "Net-(LED12-PadA)") (class "Default")
      (node (ref "LED12") (pin "A") (pinfunction "A_A") (pintype "passive"))
      (node (ref "R22") (pin "1") (pinfunction "1_1") (pintype "passive"))
    )
    (net (code "70") (name "Net-(LED13-C)") (class "Default")
      (node (ref "C7") (pin "+") (pinfunction "+_+") (pintype "passive"))
      (node (ref "LED13") (pin "K") (pinfunction "C_K") (pintype "passive"))
      (node (ref "T7") (pin "3") (pinfunction "C_3") (pintype "passive"))
    )
    (net (code "71") (name "Net-(LED13-PadA)") (class "Default")
      (node (ref "LED13") (pin "A") (pinfunction "A_A") (pintype "passive"))
      (node (ref "R24") (pin "1") (pinfunction "1_1") (pintype "passive"))
    )
    (net (code "72") (name "Net-(LED14-PadA)") (class "Default")
      (node (ref "LED14") (pin "A") (pinfunction "A_A") (pintype "passive"))
      (node (ref "R42") (pin "1") (pinfunction "1_1") (pintype "passive"))
    )
    (net (code "73") (name "Net-(LED15-PadA)") (class "Default")
      (node (ref "LED15") (pin "A") (pinfunction "A_A") (pintype "passive"))
      (node (ref "R47") (pin "1") (pinfunction "1_1") (pintype "passive"))
    )
    (net (code "74") (name "Net-(LED16-PadA)") (class "Default")
      (node (ref "LED16") (pin "A") (pinfunction "A_A") (pintype "passive"))
      (node (ref "R48") (pin "1") (pinfunction "1_1") (pintype "passive"))
    )
    (net (code "75") (name "Net-(LED17-PadA)") (class "Default")
      (node (ref "LED17") (pin "A") (pinfunction "A_A") (pintype "passive"))
      (node (ref "R49") (pin "1") (pinfunction "1_1") (pintype "passive"))
    )
    (net (code "76") (name "Net-(LED18-PadA)") (class "Default")
      (node (ref "LED18") (pin "A") (pinfunction "A_A") (pintype "passive"))
      (node (ref "R50") (pin "1") (pinfunction "1_1") (pintype "passive"))
    )
    (net (code "77") (name "Net-(LED19-PadA)") (class "Default")
      (node (ref "LED19") (pin "A") (pinfunction "A_A") (pintype "passive"))
      (node (ref "R51") (pin "1") (pinfunction "1_1") (pintype "passive"))
    )
    (net (code "78") (name "Net-(LED20-PadA)") (class "Default")
      (node (ref "LED20") (pin "A") (pinfunction "A_A") (pintype "passive"))
      (node (ref "R52") (pin "1") (pinfunction "1_1") (pintype "passive"))
    )
    (net (code "79") (name "Net-(LED21-PadA)") (class "Default")
      (node (ref "LED21") (pin "A") (pinfunction "A_A") (pintype "passive"))
      (node (ref "R53") (pin "1") (pinfunction "1_1") (pintype "passive"))
    )
    (net (code "80") (name "Net-(LED22-PadA)") (class "Default")
      (node (ref "LED22") (pin "A") (pinfunction "A_A") (pintype "passive"))
      (node (ref "R54") (pin "1") (pinfunction "1_1") (pintype "passive"))
    )
    (net (code "81") (name "Net-(LED23-PadA)") (class "Default")
      (node (ref "LED23") (pin "A") (pinfunction "A_A") (pintype "passive"))
      (node (ref "R55") (pin "1") (pinfunction "1_1") (pintype "passive"))
    )
    (net (code "82") (name "Net-(LED24-PadA)") (class "Default")
      (node (ref "LED24") (pin "A") (pinfunction "A_A") (pintype "passive"))
      (node (ref "R56") (pin "1") (pinfunction "1_1") (pintype "passive"))
    )
    (net (code "83") (name "Net-(LED25-PadA)") (class "Default")
      (node (ref "LED25") (pin "A") (pinfunction "A_A") (pintype "passive"))
      (node (ref "R57") (pin "1") (pinfunction "1_1") (pintype "passive"))
    )
    (net (code "84") (name "Net-(LED26-PadA)") (class "Default")
      (node (ref "LED26") (pin "A") (pinfunction "A_A") (pintype "passive"))
      (node (ref "R58") (pin "1") (pinfunction "1_1") (pintype "passive"))
    )
    (net (code "85") (name "Net-(LED27-PadA)") (class "Default")
      (node (ref "LED27") (pin "A") (pinfunction "A_A") (pintype "passive"))
      (node (ref "R59") (pin "1") (pinfunction "1_1") (pintype "passive"))
    )
    (net (code "86") (name "Net-(LED29-PadA)") (class "Default")
      (node (ref "LED29") (pin "A") (pinfunction "A_A") (pintype "passive"))
      (node (ref "R65") (pin "1") (pinfunction "1_1") (pintype "passive"))
    )
    (net (code "87") (name "Net-(R1-PadS)") (class "Default")
      (node (ref "R1") (pin "S") (pinfunction "S_S") (pintype "passive"))
      (node (ref "R2") (pin "2") (pinfunction "2_2") (pintype "passive"))
    )
    (net (code "88") (name "Net-(R10-Pad1)") (class "Default")
      (node (ref "R10") (pin "1") (pinfunction "1_1") (pintype "passive"))
      (node (ref "R11") (pin "2") (pinfunction "2_2") (pintype "passive"))
    )
    (net (code "89") (name "Net-(R11-Pad1)") (class "Default")
      (node (ref "R11") (pin "1") (pinfunction "1_1") (pintype "passive"))
      (node (ref "R12") (pin "2") (pinfunction "2_2") (pintype "passive"))
    )
    (net (code "90") (name "Net-(R43-Pad1)") (class "Default")
      (node (ref "R43") (pin "1") (pinfunction "1_1") (pintype "passive"))
      (node (ref "X2") (pin "2") (pinfunction "2_2") (pintype "passive"))
    )
    (net (code "91") (name "Net-(R44-Pad1)") (class "Default")
      (node (ref "R44") (pin "1") (pinfunction "1_1") (pintype "passive"))
      (node (ref "X2") (pin "3") (pinfunction "3_3") (pintype "passive"))
    )
    (net (code "92") (name "Net-(S2-2)") (class "Default")
      (node (ref "C1") (pin "+") (pinfunction "+_+") (pintype "passive"))
      (node (ref "S1") (pin "1") (pinfunction "1_1") (pintype "passive"))
      (node (ref "S2") (pin "3") (pinfunction "2_3") (pintype "passive"))
    )
    (net (code "93") (name "Net-(T1-B)") (class "Default")
      (node (ref "R6") (pin "1") (pinfunction "1_1") (pintype "passive"))
      (node (ref "T1") (pin "2") (pinfunction "B_2") (pintype "passive"))
    )
    (net (code "94") (name "Net-(T2-B)") (class "Default")
      (node (ref "C5") (pin "-") (pinfunction "-_-") (pintype "passive"))
      (node (ref "R15") (pin "1") (pinfunction "1_1") (pintype "passive"))
      (node (ref "T2") (pin "2") (pinfunction "B_2") (pintype "passive"))
    )
    (net (code "95") (name "Net-(T3-B)") (class "Default")
      (node (ref "C2") (pin "-") (pinfunction "-_-") (pintype "passive"))
      (node (ref "R17") (pin "1") (pinfunction "1_1") (pintype "passive"))
      (node (ref "T3") (pin "2") (pinfunction "B_2") (pintype "passive"))
    )
    (net (code "96") (name "Net-(T4-B)") (class "Default")
      (node (ref "C3") (pin "-") (pinfunction "-_-") (pintype "passive"))
      (node (ref "R19") (pin "1") (pinfunction "1_1") (pintype "passive"))
      (node (ref "T4") (pin "2") (pinfunction "B_2") (pintype "passive"))
    )
    (net (code "97") (name "Net-(T5-B)") (class "Default")
      (node (ref "C4") (pin "-") (pinfunction "-_-") (pintype "passive"))
      (node (ref "R21") (pin "1") (pinfunction "1_1") (pintype "passive"))
      (node (ref "T5") (pin "2") (pinfunction "B_2") (pintype "passive"))
    )
    (net (code "98") (name "Net-(T6-B)") (class "Default")
      (node (ref "C7") (pin "-") (pinfunction "-_-") (pintype "passive"))
      (node (ref "R23") (pin "1") (pinfunction "1_1") (pintype "passive"))
      (node (ref "T6") (pin "2") (pinfunction "B_2") (pintype "passive"))
    )
    (net (code "99") (name "Net-(T7-B)") (class "Default")
      (node (ref "C6") (pin "-") (pinfunction "-_-") (pintype "passive"))
      (node (ref "R25") (pin "1") (pinfunction "1_1") (pintype "passive"))
      (node (ref "T7") (pin "2") (pinfunction "B_2") (pintype "passive"))
    )
    (net (code "100") (name "OUT") (class "Default")
      (node (ref "IC10") (pin "1") (pinfunction "J(OUTPUT)_1") (pintype "bidirectional"))
      (node (ref "IC11") (pin "12") (pinfunction "Q_12") (pintype "output"))
      (node (ref "IC12") (pin "1") (pinfunction "J(OUTPUT)_1") (pintype "bidirectional"))
      (node (ref "IC13") (pin "1") (pinfunction "J(OUTPUT)_1") (pintype "bidirectional"))
      (node (ref "R47") (pin "2") (pinfunction "2_2") (pintype "passive"))
      (node (ref "R50") (pin "2") (pinfunction "2_2") (pintype "passive"))
      (node (ref "R53") (pin "2") (pinfunction "2_2") (pintype "passive"))
      (node (ref "R56") (pin "2") (pinfunction "2_2") (pintype "passive"))
    )
    (net (code "101") (name "TRIG") (class "Default")
      (node (ref "C18") (pin "+") (pinfunction "+_+") (pintype "passive"))
      (node (ref "IC14") (pin "2") (pinfunction "TRI_2") (pintype "input"))
      (node (ref "IC16") (pin "2") (pinfunction "TRI_2") (pintype "input"))
      (node (ref "IC16") (pin "6") (pinfunction "TRE_6") (pintype "input"))
      (node (ref "R60") (pin "1") (pinfunction "1_1") (pintype "passive"))
      (node (ref "R67") (pin "A") (pinfunction "A_A") (pintype "passive"))
      (node (ref "R67") (pin "S") (pinfunction "S_S") (pintype "passive"))
      (node (ref "S12") (pin "3") (pinfunction "2_3") (pintype "passive"))
    )
    (net (code "102") (name "unconnected-(IC11A-CL-Pad2)") (class "Default")
      (node (ref "IC11") (pin "2") (pinfunction "CL_2") (pintype "input"))
    )
    (net (code "103") (name "unconnected-(IC11A-~{Q}-Pad13)") (class "Default")
      (node (ref "IC11") (pin "13") (pinfunction "~{Q}_13") (pintype "output"))
    )
    (net (code "104") (name "unconnected-(S7-L1-Pad1)") (class "Default")
      (node (ref "S7") (pin "1") (pinfunction "L1_1") (pintype "passive"))
    )
    (net (code "105") (name "unconnected-(S7-L2-Pad3)") (class "Default")
      (node (ref "S7") (pin "3") (pinfunction "L2_3") (pintype "passive"))
    )
    (net (code "106") (name "unconnected-(S7-LC-Pad2)") (class "Default")
      (node (ref "S7") (pin "2") (pinfunction "LC_2") (pintype "passive"))
    )
    (net (code "107") (name "unconnected-(S7-R1-Pad4)") (class "Default")
      (node (ref "S7") (pin "4") (pinfunction "R1_4") (pintype "passive"))
    )
    (net (code "108") (name "unconnected-(S10-L1-Pad1)") (class "Default")
      (node (ref "S10") (pin "1") (pinfunction "L1_1") (pintype "passive"))
    )
    (net (code "109") (name "unconnected-(S10-R1-Pad4)") (class "Default")
      (node (ref "S10") (pin "4") (pinfunction "R1_4") (pintype "passive"))
    )
    (net (code "110") (name "unconnected-(S10-R2-Pad6)") (class "Default")
      (node (ref "S10") (pin "6") (pinfunction "R2_6") (pintype "passive"))
    )
    (net (code "111") (name "unconnected-(S10-RC-Pad5)") (class "Default")
      (node (ref "S10") (pin "5") (pinfunction "RC_5") (pintype "passive"))
    )
  )
)
